# MARK-II_board.net
KiCad netlist of a schematic drawn in EAGLE
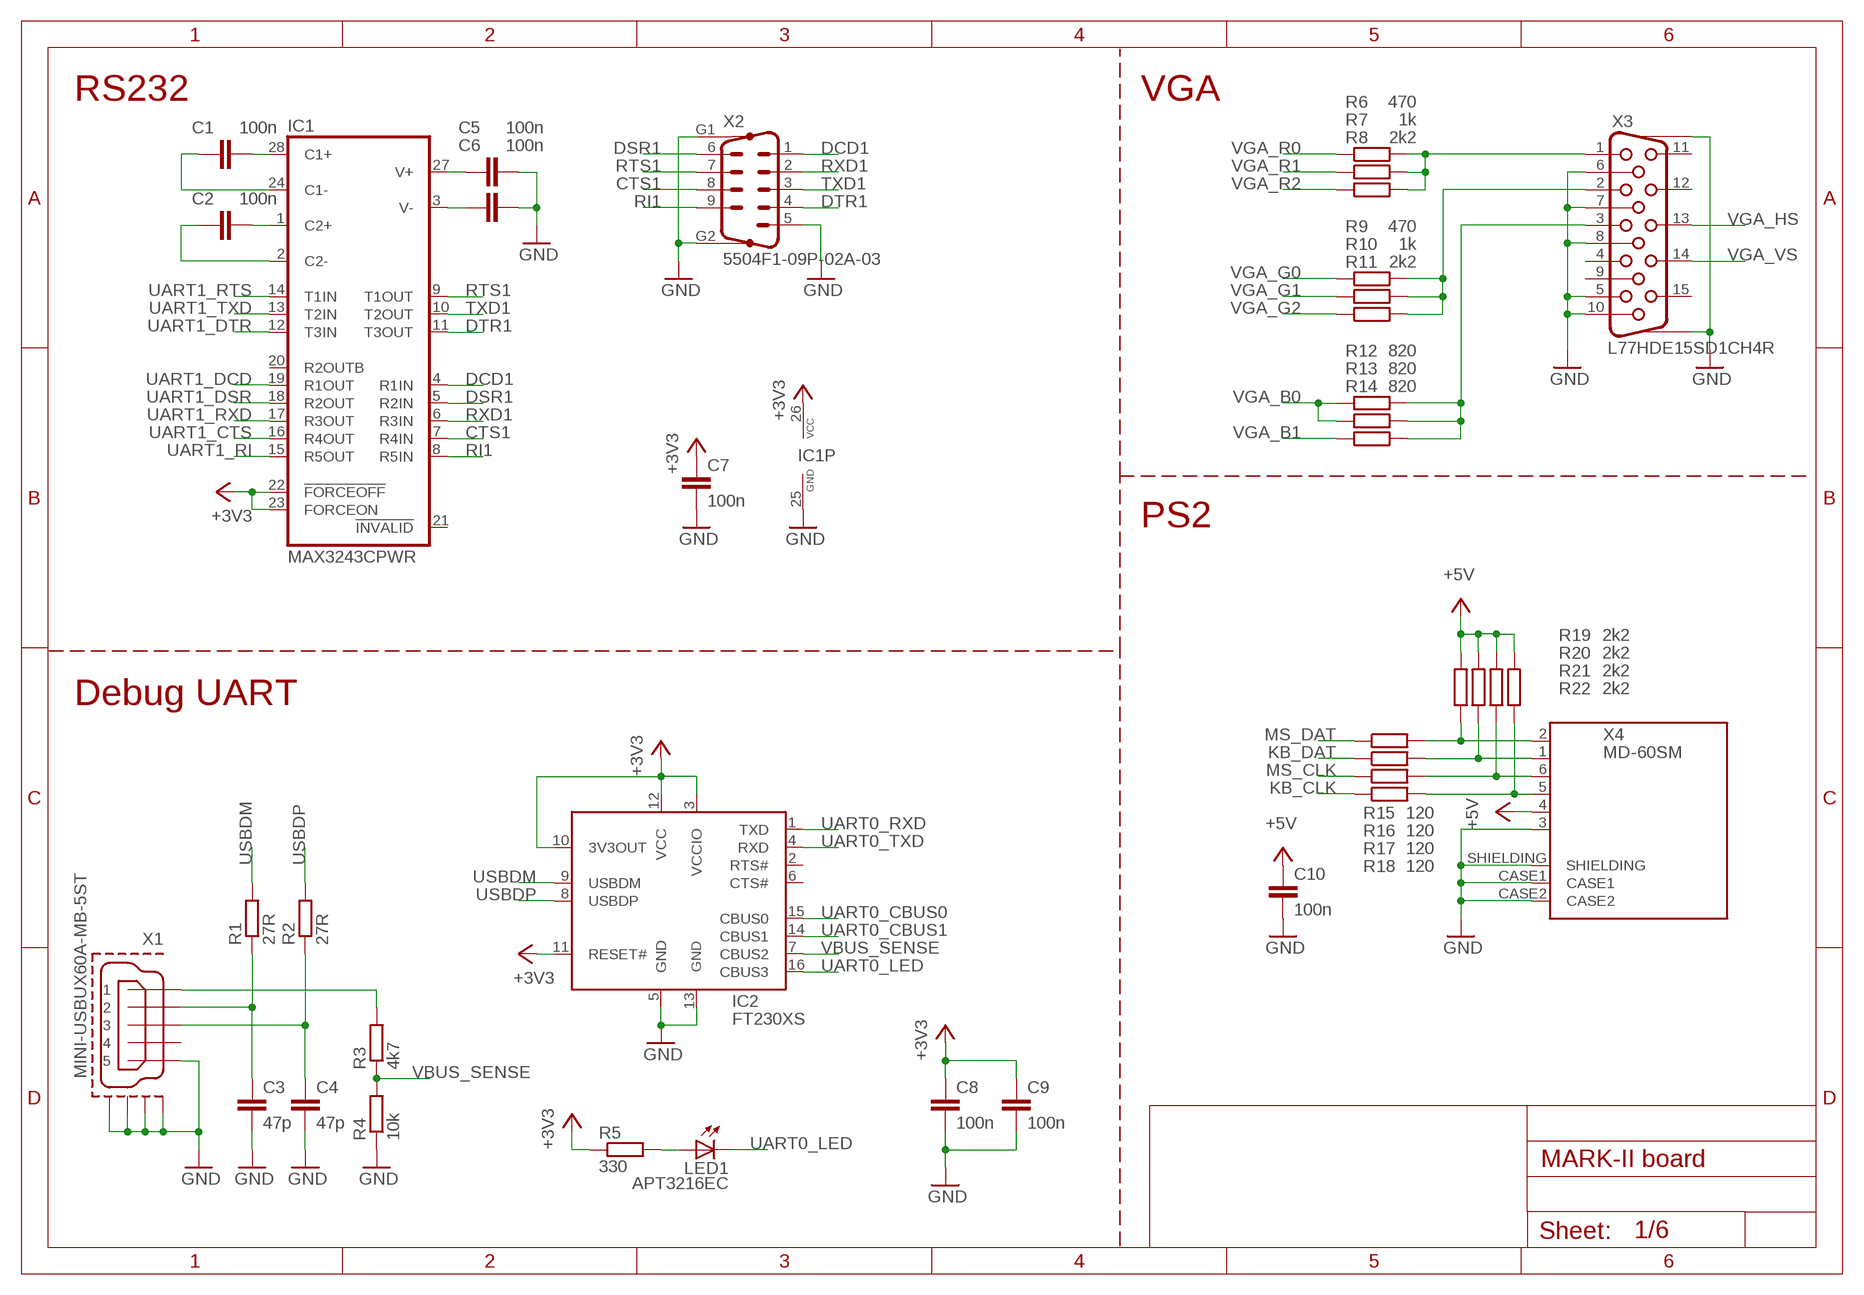
[diagram p0: schematic, sheet 1]
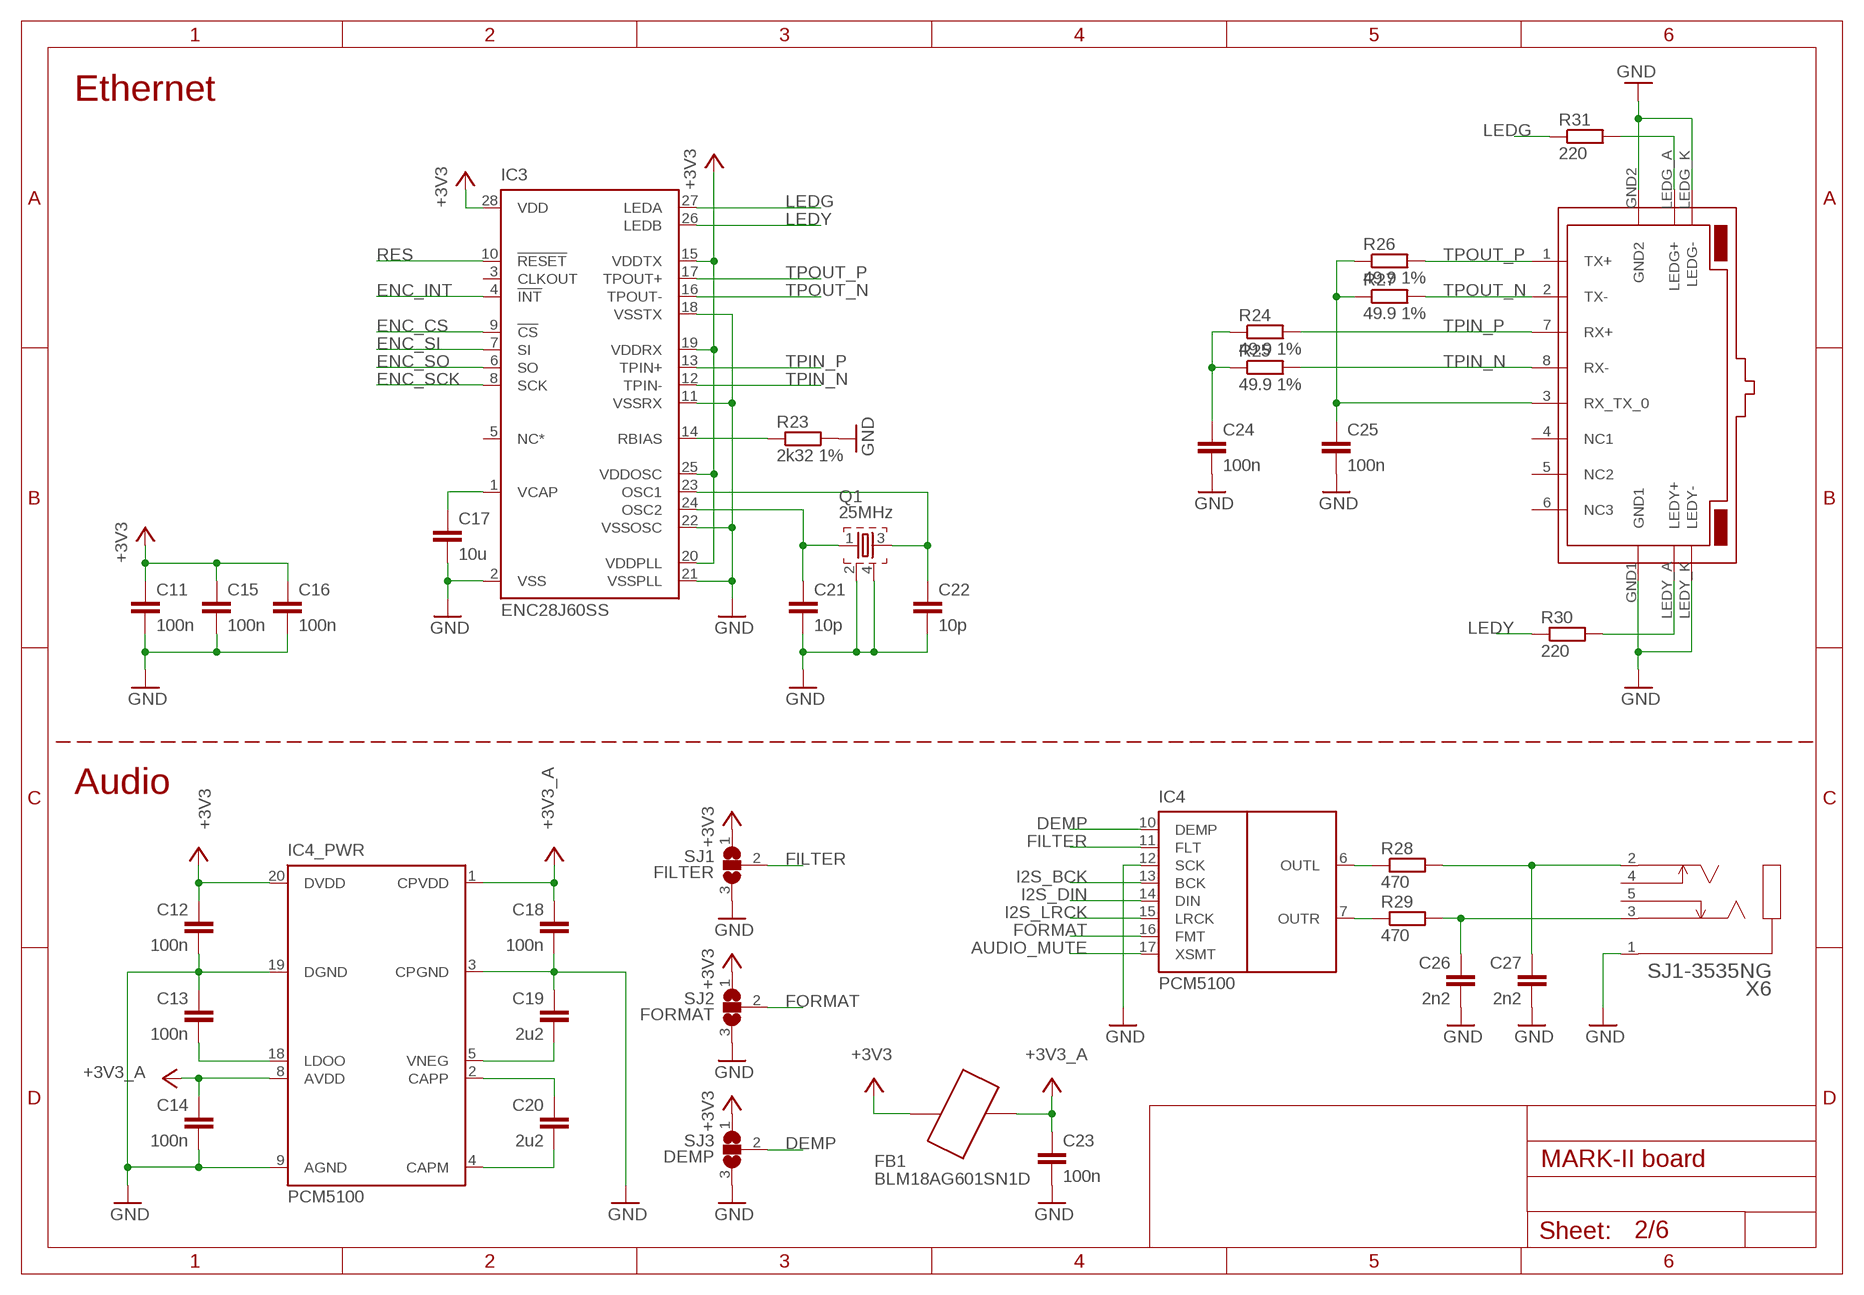
[diagram p1: schematic, sheet 2]
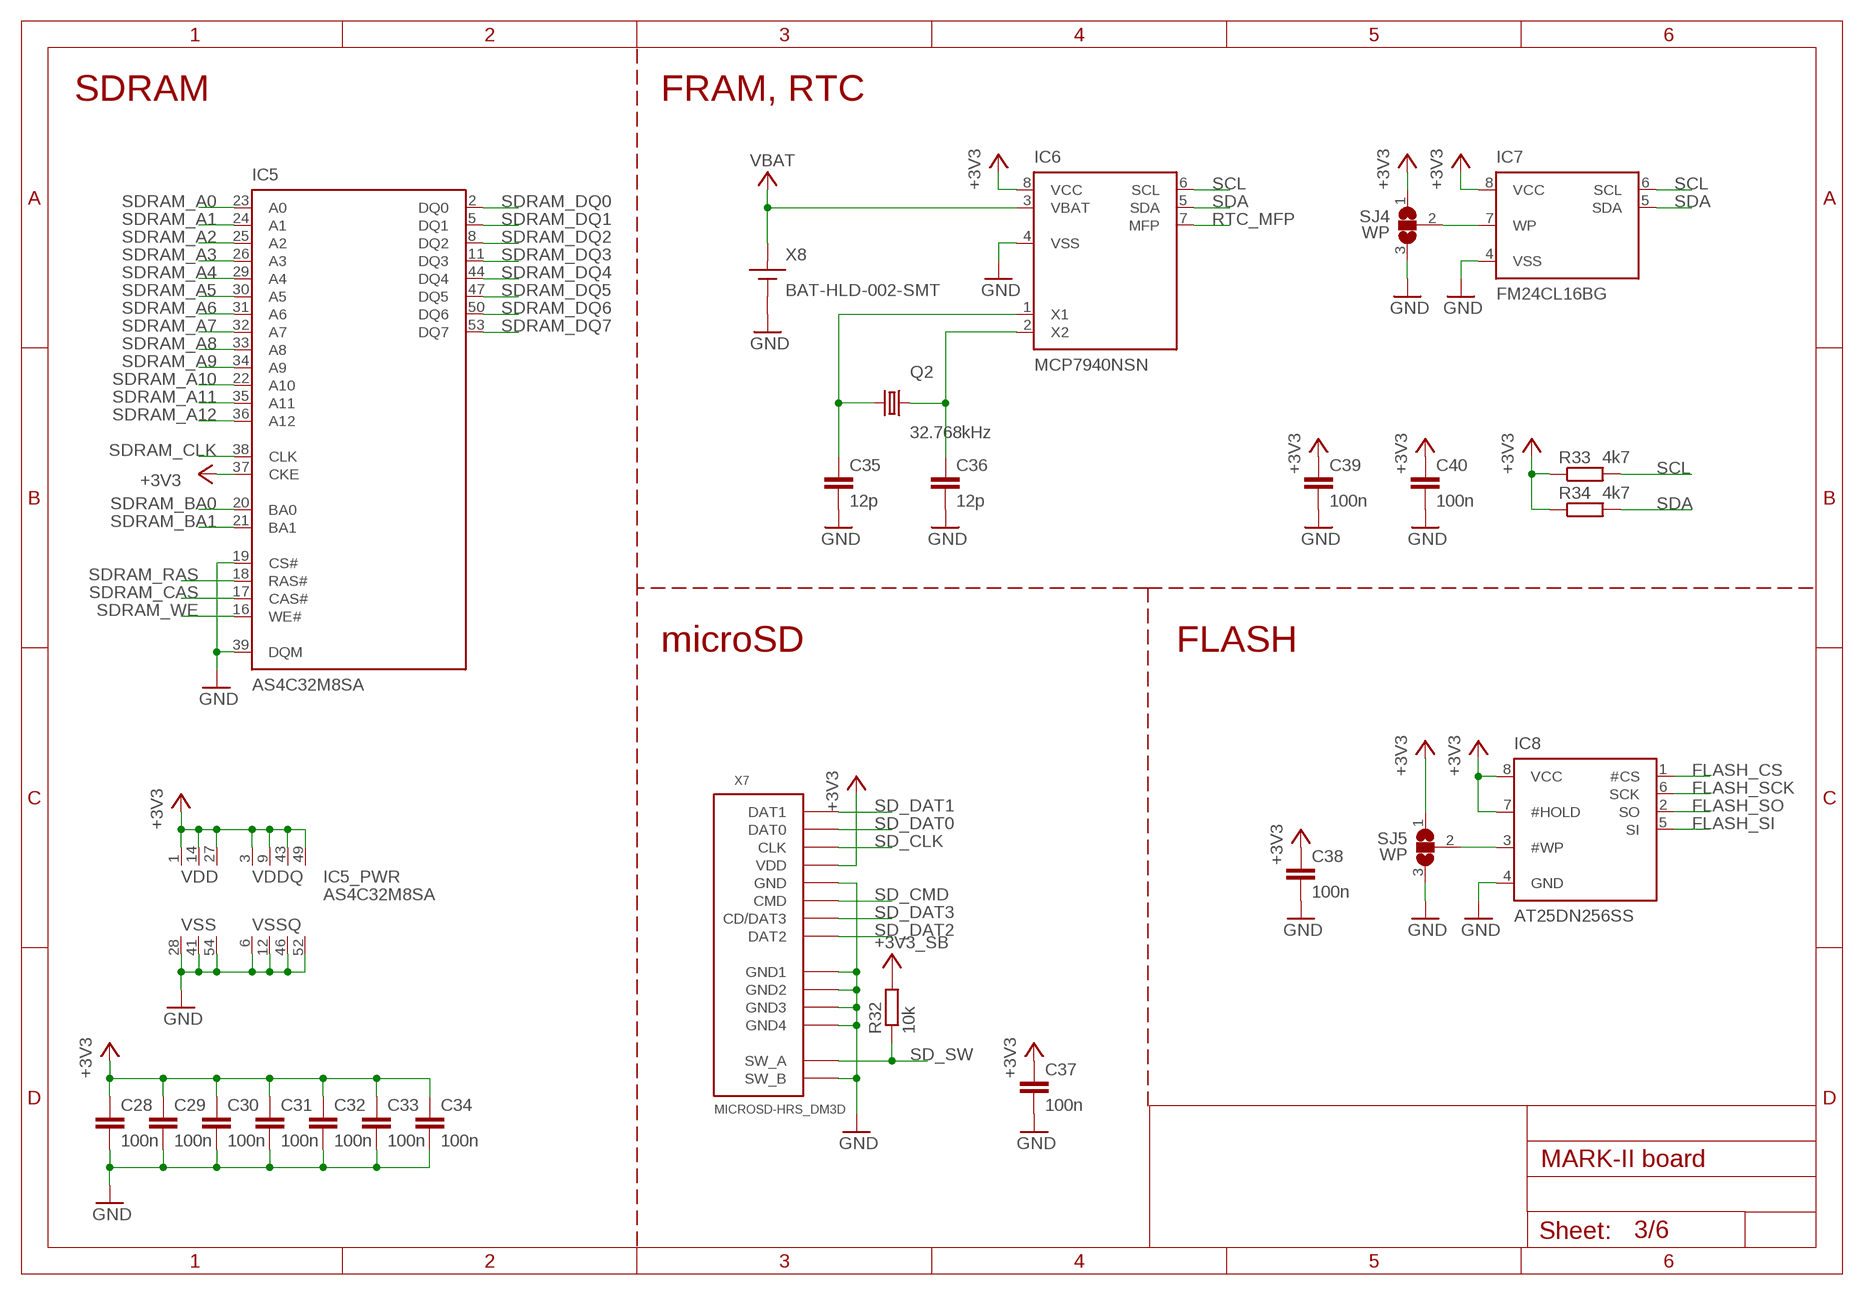
[diagram p2: schematic, sheet 3]
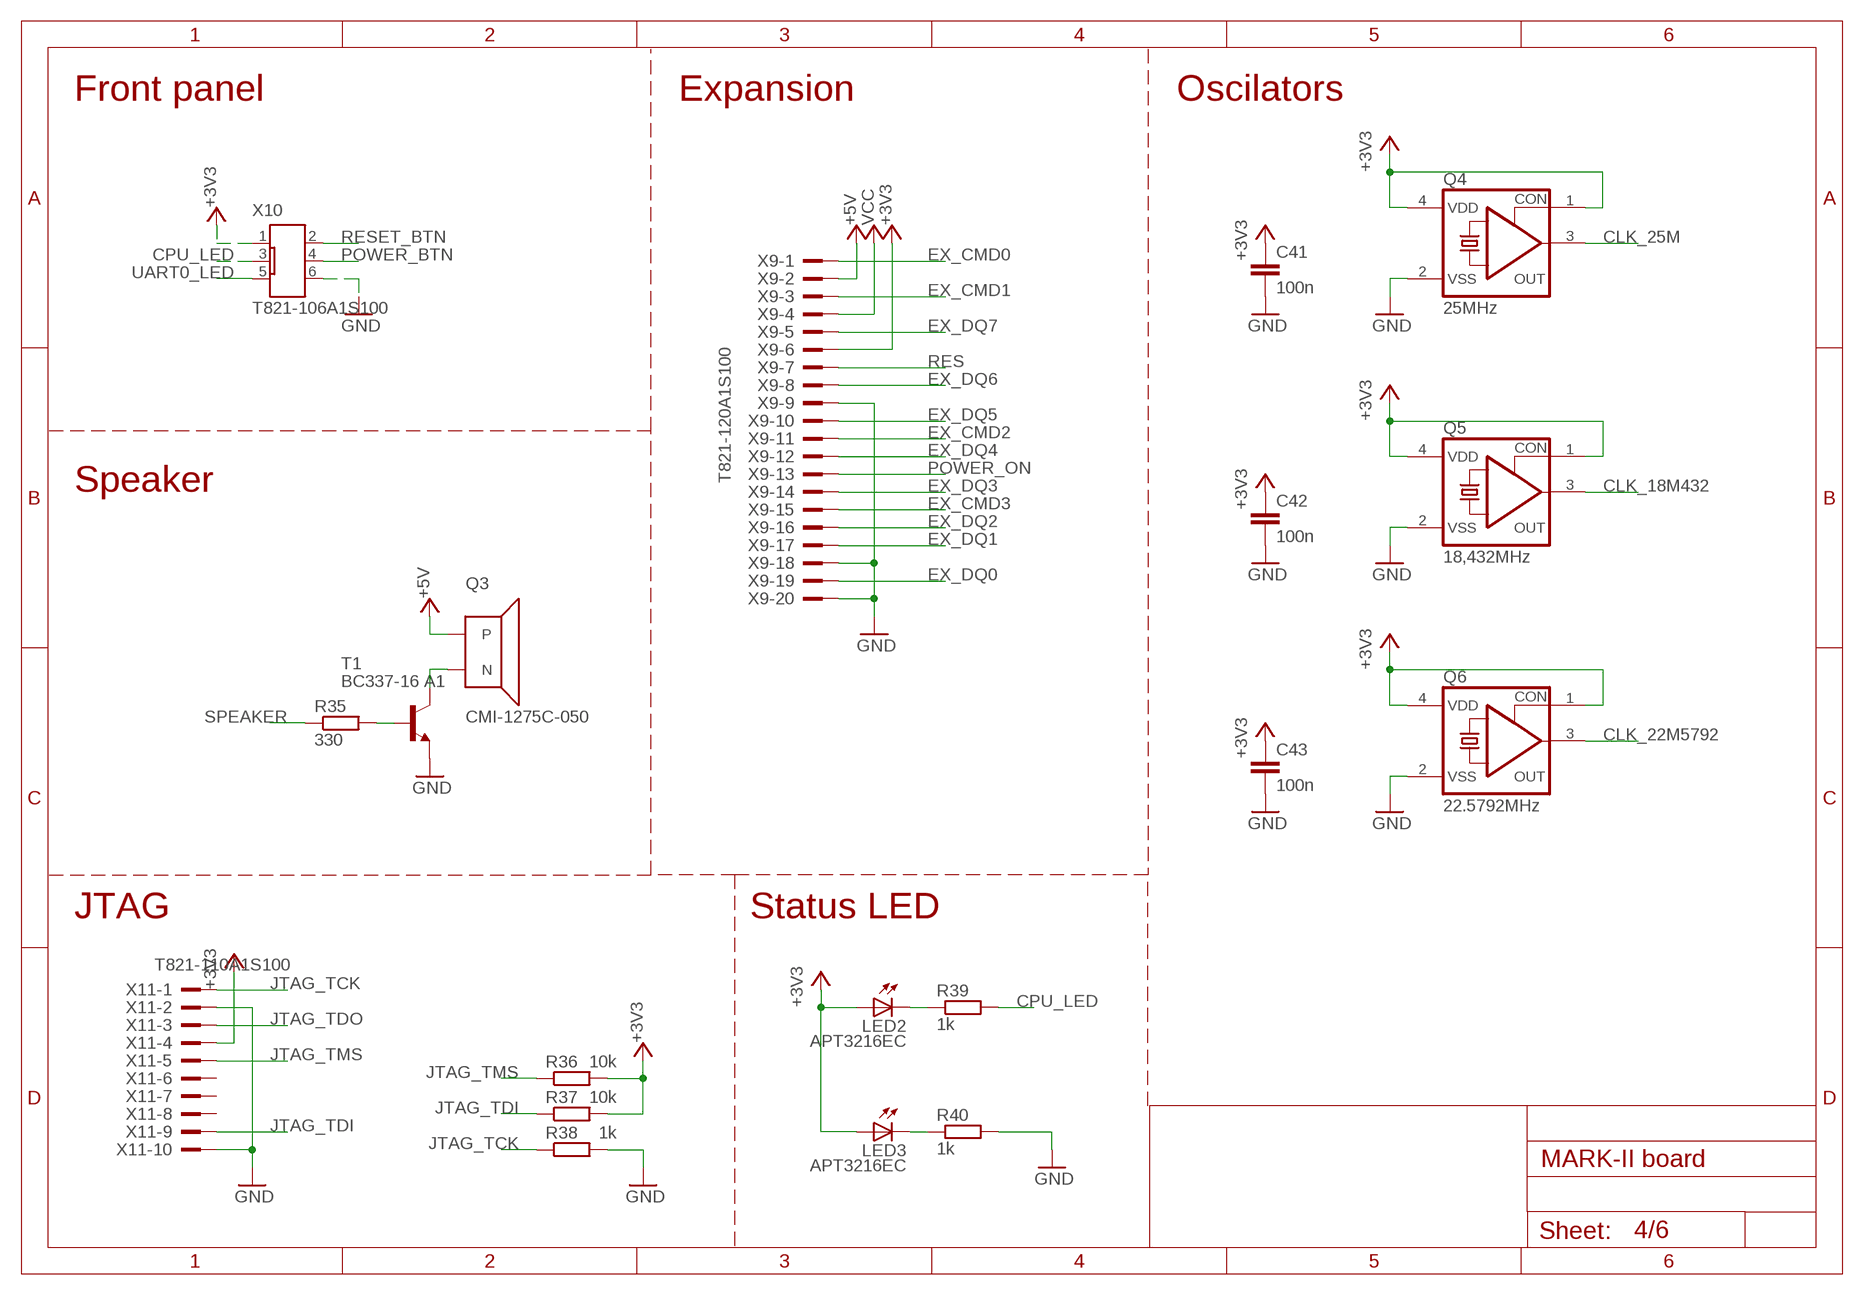
[diagram p3: schematic, sheet 4]
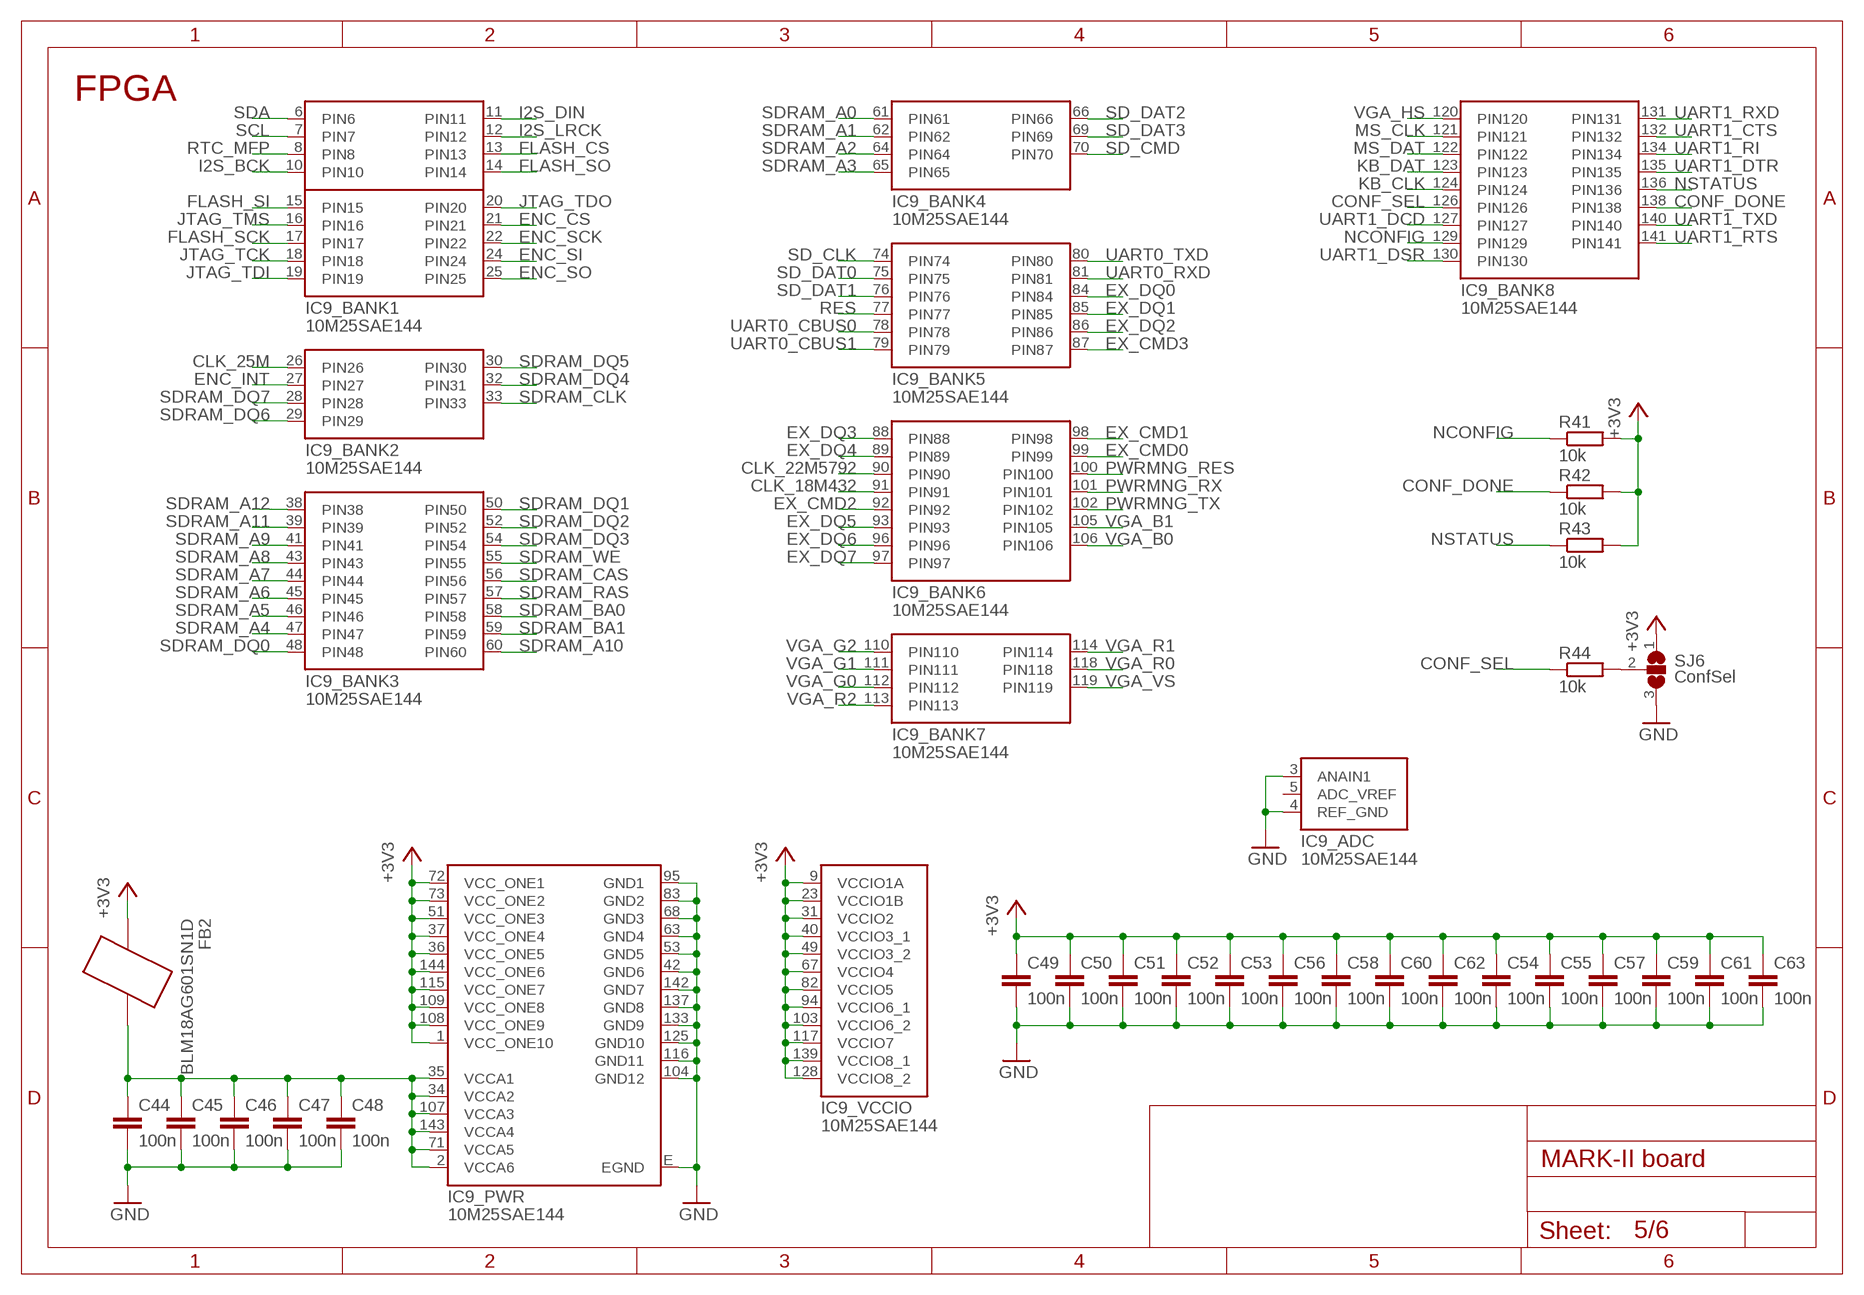
[diagram p4: schematic, sheet 5]
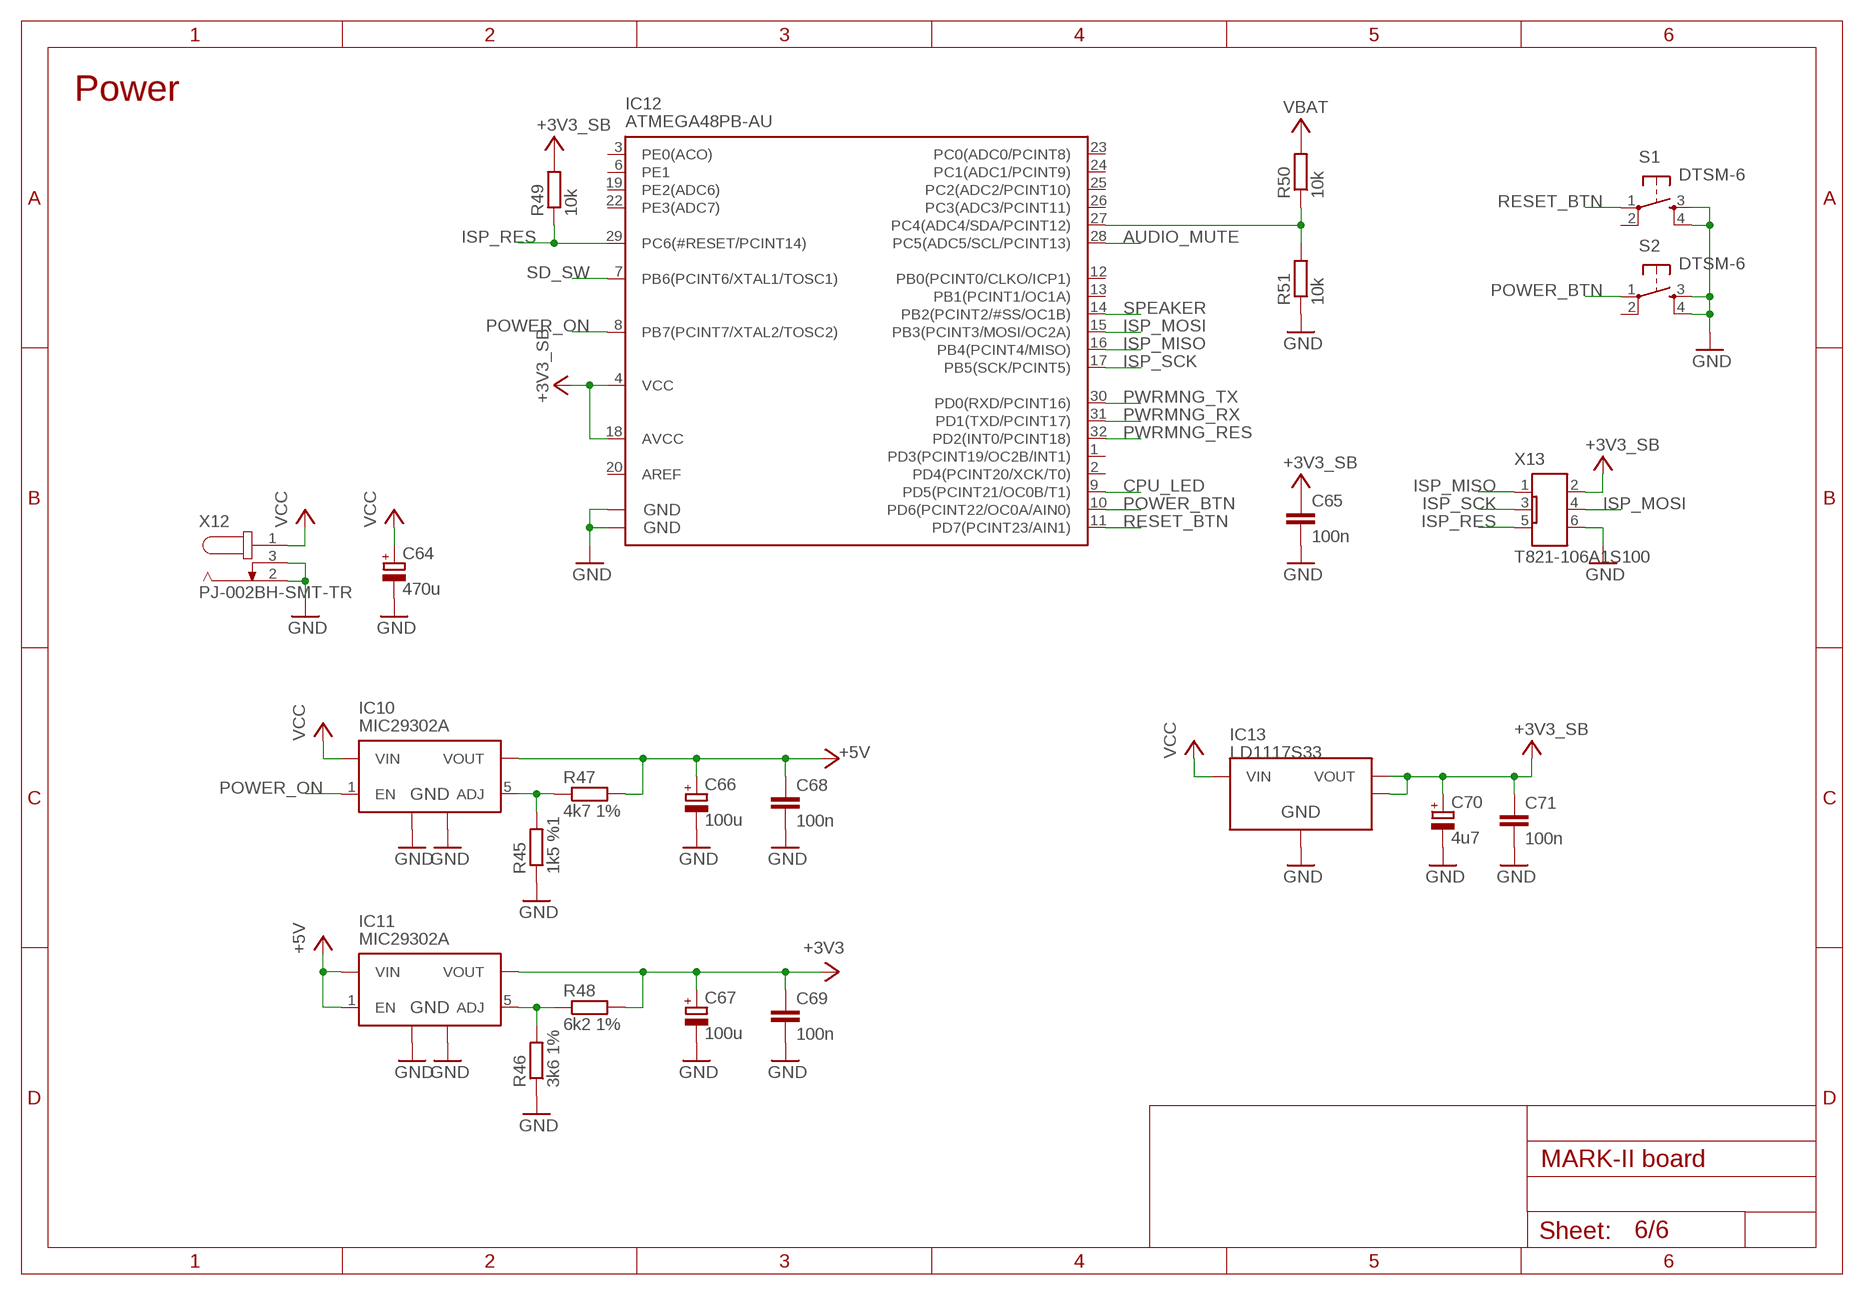
[diagram p5: schematic, sheet 6]

(export (version "E")
  (design (tool "Eeschema 10.0.6"))
  (components
    (comp (ref "C1")
      (value "100n")
      (footprint "eagle-import:C0603")
      (libsource (lib "eagle-import") (part "CC0603"))
    )
    (comp (ref "C2")
      (value "100n")
      (footprint "eagle-import:C0603")
      (libsource (lib "eagle-import") (part "CC0603"))
    )
    (comp (ref "C3")
      (value "47p")
      (footprint "eagle-import:C0603")
      (libsource (lib "eagle-import") (part "CC0603"))
    )
    (comp (ref "C4")
      (value "47p")
      (footprint "eagle-import:C0603")
      (libsource (lib "eagle-import") (part "CC0603"))
    )
    (comp (ref "C5")
      (value "100n")
      (footprint "eagle-import:C0603")
      (libsource (lib "eagle-import") (part "CC0603"))
    )
    (comp (ref "C6")
      (value "100n")
      (footprint "eagle-import:C0603")
      (libsource (lib "eagle-import") (part "CC0603"))
    )
    (comp (ref "C7")
      (value "100n")
      (footprint "eagle-import:C0603")
      (libsource (lib "eagle-import") (part "CC0603"))
    )
    (comp (ref "C8")
      (value "100n")
      (footprint "eagle-import:C0603")
      (libsource (lib "eagle-import") (part "CC0603"))
    )
    (comp (ref "C9")
      (value "100n")
      (footprint "eagle-import:C0603")
      (libsource (lib "eagle-import") (part "CC0603"))
    )
    (comp (ref "C10")
      (value "100n")
      (footprint "eagle-import:C0603")
      (libsource (lib "eagle-import") (part "CC0603"))
    )
    (comp (ref "IC1")
      (value "MAX3243CPWR")
      (footprint "eagle-import:TSSOP28")
      (fields (field (name "MOUSER") "595-MAX3243CPWR"))
      (libsource (lib "eagle-import") (part "MAX3243UI"))
    )
    (comp (ref "IC2")
      (value "FT230XS")
      (footprint "eagle-import:SSOP16")
      (libsource (lib "eagle-import") (part "FT230XS"))
    )
    (comp (ref "LED1")
      (value "APT3216EC")
      (footprint "eagle-import:1206")
      (libsource (lib "eagle-import") (part "LEDSMD"))
    )
    (comp (ref "R1")
      (value "27R")
      (footprint "eagle-import:R0603")
      (libsource (lib "eagle-import") (part "RR0603"))
    )
    (comp (ref "R2")
      (value "27R")
      (footprint "eagle-import:R0603")
      (libsource (lib "eagle-import") (part "RR0603"))
    )
    (comp (ref "R3")
      (value "4k7")
      (footprint "eagle-import:R0603")
      (libsource (lib "eagle-import") (part "RR0603"))
    )
    (comp (ref "R4")
      (value "10k")
      (footprint "eagle-import:R0603")
      (libsource (lib "eagle-import") (part "RR0603"))
    )
    (comp (ref "R5")
      (value "330")
      (footprint "eagle-import:R0603")
      (libsource (lib "eagle-import") (part "RR0603"))
    )
    (comp (ref "R6")
      (value "470")
      (footprint "eagle-import:R0603")
      (libsource (lib "eagle-import") (part "RR0603"))
    )
    (comp (ref "R7")
      (value "1k")
      (footprint "eagle-import:R0603")
      (libsource (lib "eagle-import") (part "RR0603"))
    )
    (comp (ref "R8")
      (value "2k2")
      (footprint "eagle-import:R0603")
      (libsource (lib "eagle-import") (part "RR0603"))
    )
    (comp (ref "R9")
      (value "470")
      (footprint "eagle-import:R0603")
      (libsource (lib "eagle-import") (part "RR0603"))
    )
    (comp (ref "R10")
      (value "1k")
      (footprint "eagle-import:R0603")
      (libsource (lib "eagle-import") (part "RR0603"))
    )
    (comp (ref "R11")
      (value "2k2")
      (footprint "eagle-import:R0603")
      (libsource (lib "eagle-import") (part "RR0603"))
    )
    (comp (ref "R12")
      (value "820")
      (footprint "eagle-import:R0603")
      (libsource (lib "eagle-import") (part "RR0603"))
    )
    (comp (ref "R13")
      (value "820")
      (footprint "eagle-import:R0603")
      (libsource (lib "eagle-import") (part "RR0603"))
    )
    (comp (ref "R14")
      (value "820")
      (footprint "eagle-import:R0603")
      (libsource (lib "eagle-import") (part "RR0603"))
    )
    (comp (ref "R15")
      (value "120")
      (footprint "eagle-import:R0603")
      (libsource (lib "eagle-import") (part "RR0603"))
    )
    (comp (ref "R16")
      (value "120")
      (footprint "eagle-import:R0603")
      (libsource (lib "eagle-import") (part "RR0603"))
    )
    (comp (ref "R17")
      (value "120")
      (footprint "eagle-import:R0603")
      (libsource (lib "eagle-import") (part "RR0603"))
    )
    (comp (ref "R18")
      (value "120")
      (footprint "eagle-import:R0603")
      (libsource (lib "eagle-import") (part "RR0603"))
    )
    (comp (ref "R19")
      (value "2k2")
      (footprint "eagle-import:R0603")
      (libsource (lib "eagle-import") (part "RR0603"))
    )
    (comp (ref "R20")
      (value "2k2")
      (footprint "eagle-import:R0603")
      (libsource (lib "eagle-import") (part "RR0603"))
    )
    (comp (ref "R21")
      (value "2k2")
      (footprint "eagle-import:R0603")
      (libsource (lib "eagle-import") (part "RR0603"))
    )
    (comp (ref "R22")
      (value "2k2")
      (footprint "eagle-import:R0603")
      (libsource (lib "eagle-import") (part "RR0603"))
    )
    (comp (ref "X1")
      (value "MINI-USBUX60A-MB-5ST")
      (footprint "eagle-import:UX60A-MB-5ST")
      (libsource (lib "eagle-import") (part "MINI-USBUX60A-MB-5ST"))
    )
    (comp (ref "X2")
      (value "5504F1-09P-02A-03")
      (footprint "eagle-import:M09HP")
      (libsource (lib "eagle-import") (part "M09"))
    )
    (comp (ref "X3")
      (value "L77HDE15SD1CH4R")
      (footprint "eagle-import:HDF15H")
      (libsource (lib "eagle-import") (part "HF15H"))
    )
    (comp (ref "X4")
      (value "MD-60SM")
      (footprint "eagle-import:MINIDIN_6_3GND")
      (libsource (lib "eagle-import") (part "MINIDIN_6"))
    )
    (comp (ref "C41")
      (value "100n")
      (footprint "eagle-import:C0603")
      (libsource (lib "eagle-import") (part "CC0603"))
    )
    (comp (ref "C42")
      (value "100n")
      (footprint "eagle-import:C0603")
      (libsource (lib "eagle-import") (part "CC0603"))
    )
    (comp (ref "C43")
      (value "100n")
      (footprint "eagle-import:C0603")
      (libsource (lib "eagle-import") (part "CC0603"))
    )
    (comp (ref "LED2")
      (value "APT3216EC")
      (footprint "eagle-import:1206")
      (libsource (lib "eagle-import") (part "LEDSMD"))
    )
    (comp (ref "LED3")
      (value "APT3216EC")
      (footprint "eagle-import:1206")
      (libsource (lib "eagle-import") (part "LEDSMD"))
    )
    (comp (ref "Q3")
      (value "CMI-1275C-050")
      (footprint "eagle-import:BUUZZER")
      (libsource (lib "eagle-import") (part "CMI-1275C-050"))
    )
    (comp (ref "Q4")
      (value "25MHz")
      (footprint "eagle-import:5.2X3.4-4-PAD")
      (libsource (lib "eagle-import") (part "OSC-OE-CFPS-9"))
    )
    (comp (ref "Q5")
      (value "18,432MHz")
      (footprint "eagle-import:5.2X3.4-4-PAD")
      (libsource (lib "eagle-import") (part "OSC-OE-CFPS-9"))
    )
    (comp (ref "Q6")
      (value "22.5792MHz")
      (footprint "eagle-import:5.2X3.4-4-PAD")
      (libsource (lib "eagle-import") (part "OSC-OE-CFPS-9"))
    )
    (comp (ref "R35")
      (value "330")
      (footprint "eagle-import:R0603")
      (libsource (lib "eagle-import") (part "RR0603"))
    )
    (comp (ref "R36")
      (value "10k")
      (footprint "eagle-import:R0603")
      (libsource (lib "eagle-import") (part "RR0603"))
    )
    (comp (ref "R37")
      (value "10k")
      (footprint "eagle-import:R0603")
      (libsource (lib "eagle-import") (part "RR0603"))
    )
    (comp (ref "R38")
      (value "1k")
      (footprint "eagle-import:R0603")
      (libsource (lib "eagle-import") (part "RR0603"))
    )
    (comp (ref "R39")
      (value "1k")
      (footprint "eagle-import:R0603")
      (libsource (lib "eagle-import") (part "RR0603"))
    )
    (comp (ref "R40")
      (value "1k")
      (footprint "eagle-import:R0603")
      (libsource (lib "eagle-import") (part "RR0603"))
    )
    (comp (ref "T1")
      (value "BC337-16 A1")
      (footprint "eagle-import:TO92")
      (libsource (lib "eagle-import") (part "BC337"))
    )
    (comp (ref "X9")
      (value "T821-120A1S100")
      (footprint "eagle-import:PAK100_2500-20")
      (fields (field (name "FARNELL") "2215309"))
      (libsource (lib "eagle-import") (part "2520-"))
    )
    (comp (ref "X10")
      (value "T821-106A1S100")
      (footprint "eagle-import:PAK100_2300-06")
      (libsource (lib "eagle-import") (part "IDC_2306"))
    )
    (comp (ref "X11")
      (value "T821-110A1S100")
      (footprint "eagle-import:PAK100_2500-10")
      (fields (field (name "FARNELL") "2215304"))
      (libsource (lib "eagle-import") (part "2510-"))
    )
    (comp (ref "C28")
      (value "100n")
      (footprint "eagle-import:C0603")
      (libsource (lib "eagle-import") (part "CC0603"))
    )
    (comp (ref "C29")
      (value "100n")
      (footprint "eagle-import:C0603")
      (libsource (lib "eagle-import") (part "CC0603"))
    )
    (comp (ref "C30")
      (value "100n")
      (footprint "eagle-import:C0603")
      (libsource (lib "eagle-import") (part "CC0603"))
    )
    (comp (ref "C31")
      (value "100n")
      (footprint "eagle-import:C0603")
      (libsource (lib "eagle-import") (part "CC0603"))
    )
    (comp (ref "C32")
      (value "100n")
      (footprint "eagle-import:C0603")
      (libsource (lib "eagle-import") (part "CC0603"))
    )
    (comp (ref "C33")
      (value "100n")
      (footprint "eagle-import:C0603")
      (libsource (lib "eagle-import") (part "CC0603"))
    )
    (comp (ref "C34")
      (value "100n")
      (footprint "eagle-import:C0603")
      (libsource (lib "eagle-import") (part "CC0603"))
    )
    (comp (ref "C35")
      (value "12p")
      (footprint "eagle-import:C0603")
      (libsource (lib "eagle-import") (part "CC0603"))
    )
    (comp (ref "C36")
      (value "12p")
      (footprint "eagle-import:C0603")
      (libsource (lib "eagle-import") (part "CC0603"))
    )
    (comp (ref "C37")
      (value "100n")
      (footprint "eagle-import:C0603")
      (libsource (lib "eagle-import") (part "CC0603"))
    )
    (comp (ref "C38")
      (value "100n")
      (footprint "eagle-import:C0603")
      (libsource (lib "eagle-import") (part "CC0603"))
    )
    (comp (ref "C39")
      (value "100n")
      (footprint "eagle-import:C0603")
      (libsource (lib "eagle-import") (part "CC0603"))
    )
    (comp (ref "C40")
      (value "100n")
      (footprint "eagle-import:C0603")
      (libsource (lib "eagle-import") (part "CC0603"))
    )
    (comp (ref "IC5")
      (value "AS4C32M8SA")
      (footprint "eagle-import:TSOP54")
      (fields (field (name "MOUSER") "913-AS4C32M8SA6TIN"))
      (libsource (lib "eagle-import") (part "IS42S83200"))
    )
    (comp (ref "IC6")
      (value "MCP7940NSN")
      (footprint "eagle-import:SOIC8")
      (libsource (lib "eagle-import") (part "MCP7940NSN"))
    )
    (comp (ref "IC7")
      (value "FM24CL16BG")
      (footprint "eagle-import:SOIC8")
      (libsource (lib "eagle-import") (part "FM24CL16BG"))
    )
    (comp (ref "IC8")
      (value "AT25DN256SS")
      (footprint "eagle-import:SOIC8")
      (libsource (lib "eagle-import") (part "AT25DN256SS"))
    )
    (comp (ref "Q2")
      (value "32.768kHz")
      (footprint "eagle-import:85SMX")
      (libsource (lib "eagle-import") (part "CRYSTALS-NOGND-85SMX"))
    )
    (comp (ref "R32")
      (value "10k")
      (footprint "eagle-import:R0603")
      (libsource (lib "eagle-import") (part "RR0603"))
    )
    (comp (ref "R33")
      (value "4k7")
      (footprint "eagle-import:R0603")
      (libsource (lib "eagle-import") (part "RR0603"))
    )
    (comp (ref "R34")
      (value "4k7")
      (footprint "eagle-import:R0603")
      (libsource (lib "eagle-import") (part "RR0603"))
    )
    (comp (ref "SJ4")
      (value "WP")
      (footprint "eagle-import:SJ_2")
      (libsource (lib "eagle-import") (part "SJ2W"))
    )
    (comp (ref "SJ5")
      (value "WP")
      (footprint "eagle-import:SJ_2")
      (libsource (lib "eagle-import") (part "SJ2W"))
    )
    (comp (ref "X7")
      (value "MICROSD-HRS_DM3D")
      (footprint "eagle-import:DM3D")
      (libsource (lib "eagle-import") (part "MICROSD-HRS_DM3D"))
    )
    (comp (ref "X8")
      (value "BAT-HLD-002-SMT")
      (footprint "eagle-import:BAT-HLD-002-SMT")
      (libsource (lib "eagle-import") (part "BAT-HLD-002-SMT"))
    )
    (comp (ref "C44")
      (value "100n")
      (footprint "eagle-import:C0603")
      (libsource (lib "eagle-import") (part "CC0603"))
    )
    (comp (ref "C45")
      (value "100n")
      (footprint "eagle-import:C0603")
      (libsource (lib "eagle-import") (part "CC0603"))
    )
    (comp (ref "C46")
      (value "100n")
      (footprint "eagle-import:C0603")
      (libsource (lib "eagle-import") (part "CC0603"))
    )
    (comp (ref "C47")
      (value "100n")
      (footprint "eagle-import:C0603")
      (libsource (lib "eagle-import") (part "CC0603"))
    )
    (comp (ref "C48")
      (value "100n")
      (footprint "eagle-import:C0603")
      (libsource (lib "eagle-import") (part "CC0603"))
    )
    (comp (ref "C49")
      (value "100n")
      (footprint "eagle-import:C0603")
      (libsource (lib "eagle-import") (part "CC0603"))
    )
    (comp (ref "C50")
      (value "100n")
      (footprint "eagle-import:C0603")
      (libsource (lib "eagle-import") (part "CC0603"))
    )
    (comp (ref "C51")
      (value "100n")
      (footprint "eagle-import:C0603")
      (libsource (lib "eagle-import") (part "CC0603"))
    )
    (comp (ref "C52")
      (value "100n")
      (footprint "eagle-import:C0603")
      (libsource (lib "eagle-import") (part "CC0603"))
    )
    (comp (ref "C53")
      (value "100n")
      (footprint "eagle-import:C0603")
      (libsource (lib "eagle-import") (part "CC0603"))
    )
    (comp (ref "C54")
      (value "100n")
      (footprint "eagle-import:C0603")
      (libsource (lib "eagle-import") (part "CC0603"))
    )
    (comp (ref "C55")
      (value "100n")
      (footprint "eagle-import:C0603")
      (libsource (lib "eagle-import") (part "CC0603"))
    )
    (comp (ref "C56")
      (value "100n")
      (footprint "eagle-import:C0603")
      (libsource (lib "eagle-import") (part "CC0603"))
    )
    (comp (ref "C57")
      (value "100n")
      (footprint "eagle-import:C0603")
      (libsource (lib "eagle-import") (part "CC0603"))
    )
    (comp (ref "C58")
      (value "100n")
      (footprint "eagle-import:C0603")
      (libsource (lib "eagle-import") (part "CC0603"))
    )
    (comp (ref "C59")
      (value "100n")
      (footprint "eagle-import:C0603")
      (libsource (lib "eagle-import") (part "CC0603"))
    )
    (comp (ref "C60")
      (value "100n")
      (footprint "eagle-import:C0603")
      (libsource (lib "eagle-import") (part "CC0603"))
    )
    (comp (ref "C61")
      (value "100n")
      (footprint "eagle-import:C0603")
      (libsource (lib "eagle-import") (part "CC0603"))
    )
    (comp (ref "C62")
      (value "100n")
      (footprint "eagle-import:C0603")
      (libsource (lib "eagle-import") (part "CC0603"))
    )
    (comp (ref "C63")
      (value "100n")
      (footprint "eagle-import:C0603")
      (libsource (lib "eagle-import") (part "CC0603"))
    )
    (comp (ref "FB2")
      (value "BLM18AG601SN1D")
      (footprint "eagle-import:R0603")
      (libsource (lib "eagle-import") (part "FERRITE_BEAD603"))
    )
    (comp (ref "IC9")
      (value "10M25SAE144")
      (footprint "eagle-import:EQFP144")
      (fields (field (name "MOUSER") "989-10M25SAE144C8G"))
      (libsource (lib "eagle-import") (part "10M25SAE144"))
    )
    (comp (ref "R41")
      (value "10k")
      (footprint "eagle-import:R0603")
      (libsource (lib "eagle-import") (part "RR0603"))
    )
    (comp (ref "R42")
      (value "10k")
      (footprint "eagle-import:R0603")
      (libsource (lib "eagle-import") (part "RR0603"))
    )
    (comp (ref "R43")
      (value "10k")
      (footprint "eagle-import:R0603")
      (libsource (lib "eagle-import") (part "RR0603"))
    )
    (comp (ref "R44")
      (value "10k")
      (footprint "eagle-import:R0603")
      (libsource (lib "eagle-import") (part "RR0603"))
    )
    (comp (ref "SJ6")
      (value "ConfSel")
      (footprint "eagle-import:SJ_2")
      (libsource (lib "eagle-import") (part "SJ2W"))
    )
    (comp (ref "C64")
      (value "470u")
      (footprint "eagle-import:E3,5-8")
      (libsource (lib "eagle-import") (part "C-POLE3.5-8"))
    )
    (comp (ref "C65")
      (value "100n")
      (footprint "eagle-import:C0603")
      (libsource (lib "eagle-import") (part "CC0603"))
    )
    (comp (ref "C66")
      (value "100u")
      (footprint "eagle-import:E2,5-7")
      (libsource (lib "eagle-import") (part "C-POLE2.5-7"))
    )
    (comp (ref "C67")
      (value "100u")
      (footprint "eagle-import:E2,5-7")
      (libsource (lib "eagle-import") (part "C-POLE2.5-7"))
    )
    (comp (ref "C68")
      (value "100n")
      (footprint "eagle-import:C0603")
      (libsource (lib "eagle-import") (part "CC0603"))
    )
    (comp (ref "C69")
      (value "100n")
      (footprint "eagle-import:C0603")
      (libsource (lib "eagle-import") (part "CC0603"))
    )
    (comp (ref "C70")
      (value "4u7")
      (footprint "eagle-import:E2,5-5")
      (libsource (lib "eagle-import") (part "C-POLE2.5-5"))
    )
    (comp (ref "C71")
      (value "100n")
      (footprint "eagle-import:C0603")
      (libsource (lib "eagle-import") (part "CC0603"))
    )
    (comp (ref "IC10")
      (value "MIC29302A")
      (footprint "eagle-import:D2PAK-5")
      (libsource (lib "eagle-import") (part "IFX1963TBV"))
    )
    (comp (ref "IC11")
      (value "MIC29302A")
      (footprint "eagle-import:D2PAK-5")
      (libsource (lib "eagle-import") (part "IFX1963TBV"))
    )
    (comp (ref "IC12")
      (value "ATMEGA48PB-AU")
      (footprint "eagle-import:TQFP32-08")
      (libsource (lib "eagle-import") (part "ATMEGA48PB-AU"))
    )
    (comp (ref "IC13")
      (value "LD1117S33")
      (footprint "eagle-import:SOT223")
      (libsource (lib "eagle-import") (part "LD1117S33"))
    )
    (comp (ref "R45")
      (value "1k5 %1")
      (footprint "eagle-import:R0603")
      (libsource (lib "eagle-import") (part "RR0603"))
    )
    (comp (ref "R46")
      (value "3k6 1%")
      (footprint "eagle-import:R0603")
      (libsource (lib "eagle-import") (part "RR0603"))
    )
    (comp (ref "R47")
      (value "4k7 1%")
      (footprint "eagle-import:R0603")
      (libsource (lib "eagle-import") (part "RR0603"))
    )
    (comp (ref "R48")
      (value "6k2 1%")
      (footprint "eagle-import:R0603")
      (libsource (lib "eagle-import") (part "RR0603"))
    )
    (comp (ref "R49")
      (value "10k")
      (footprint "eagle-import:R0603")
      (libsource (lib "eagle-import") (part "RR0603"))
    )
    (comp (ref "R50")
      (value "10k")
      (footprint "eagle-import:R0603")
      (libsource (lib "eagle-import") (part "RR0603"))
    )
    (comp (ref "R51")
      (value "10k")
      (footprint "eagle-import:R0603")
      (libsource (lib "eagle-import") (part "RR0603"))
    )
    (comp (ref "S1")
      (value "DTSM-6")
      (footprint "eagle-import:DTSM-6")
      (libsource (lib "eagle-import") (part "DTSM-6"))
    )
    (comp (ref "S2")
      (value "DTSM-6")
      (footprint "eagle-import:DTSM-6")
      (libsource (lib "eagle-import") (part "DTSM-6"))
    )
    (comp (ref "X12")
      (value "PJ-002BH-SMT-TR")
      (footprint "eagle-import:PJ-002BH-SMT")
      (libsource (lib "eagle-import") (part "PJ-002BH-SMT"))
    )
    (comp (ref "X13")
      (value "T821-106A1S100")
      (footprint "eagle-import:PAK100_2300-06")
      (libsource (lib "eagle-import") (part "IDC_2306"))
    )
    (comp (ref "C11")
      (value "100n")
      (footprint "eagle-import:C0603")
      (libsource (lib "eagle-import") (part "CC0603"))
    )
    (comp (ref "C12")
      (value "100n")
      (footprint "eagle-import:C0603")
      (libsource (lib "eagle-import") (part "CC0603"))
    )
    (comp (ref "C13")
      (value "100n")
      (footprint "eagle-import:C0603")
      (libsource (lib "eagle-import") (part "CC0603"))
    )
    (comp (ref "C14")
      (value "100n")
      (footprint "eagle-import:C0603")
      (libsource (lib "eagle-import") (part "CC0603"))
    )
    (comp (ref "C15")
      (value "100n")
      (footprint "eagle-import:C0603")
      (libsource (lib "eagle-import") (part "CC0603"))
    )
    (comp (ref "C16")
      (value "100n")
      (footprint "eagle-import:C0603")
      (libsource (lib "eagle-import") (part "CC0603"))
    )
    (comp (ref "C17")
      (value "10u")
      (footprint "eagle-import:C0603")
      (libsource (lib "eagle-import") (part "CC0603"))
    )
    (comp (ref "C18")
      (value "100n")
      (footprint "eagle-import:C0603")
      (libsource (lib "eagle-import") (part "CC0603"))
    )
    (comp (ref "C19")
      (value "2u2")
      (footprint "eagle-import:C0603")
      (libsource (lib "eagle-import") (part "CC0603"))
    )
    (comp (ref "C20")
      (value "2u2")
      (footprint "eagle-import:C0603")
      (libsource (lib "eagle-import") (part "CC0603"))
    )
    (comp (ref "C21")
      (value "10p")
      (footprint "eagle-import:C0603")
      (libsource (lib "eagle-import") (part "CC0603"))
    )
    (comp (ref "C22")
      (value "10p")
      (footprint "eagle-import:C0603")
      (libsource (lib "eagle-import") (part "CC0603"))
    )
    (comp (ref "C23")
      (value "100n")
      (footprint "eagle-import:C0603")
      (libsource (lib "eagle-import") (part "CC0603"))
    )
    (comp (ref "C24")
      (value "100n")
      (footprint "eagle-import:C0603")
      (libsource (lib "eagle-import") (part "CC0603"))
    )
    (comp (ref "C25")
      (value "100n")
      (footprint "eagle-import:C0603")
      (libsource (lib "eagle-import") (part "CC0603"))
    )
    (comp (ref "C26")
      (value "2n2")
      (footprint "eagle-import:C0603")
      (libsource (lib "eagle-import") (part "CC0603"))
    )
    (comp (ref "C27")
      (value "2n2")
      (footprint "eagle-import:C0603")
      (libsource (lib "eagle-import") (part "CC0603"))
    )
    (comp (ref "FB1")
      (value "BLM18AG601SN1D")
      (footprint "eagle-import:R0603")
      (libsource (lib "eagle-import") (part "FERRITE_BEAD603"))
    )
    (comp (ref "IC3")
      (value "ENC28J60SS")
      (footprint "eagle-import:SSOP28")
      (libsource (lib "eagle-import") (part "ENC28J60SS"))
    )
    (comp (ref "IC4")
      (value "PCM5100")
      (footprint "eagle-import:TSSOP20")
      (fields (field (name "MOUSER") "595-PCM5100APWR"))
      (libsource (lib "eagle-import") (part "PCM5100"))
    )
    (comp (ref "Q1")
      (value "25MHz")
      (footprint "eagle-import:3.4X2.7-4-PAD")
      (libsource (lib "eagle-import") (part "CRYSTALS-GND-LID-CFPX-180"))
    )
    (comp (ref "R23")
      (value "2k32 1%")
      (footprint "eagle-import:R0603")
      (libsource (lib "eagle-import") (part "RR0603"))
    )
    (comp (ref "R24")
      (value "49.9 1%")
      (footprint "eagle-import:R0603")
      (libsource (lib "eagle-import") (part "RR0603"))
    )
    (comp (ref "R25")
      (value "49.9 1%")
      (footprint "eagle-import:R0603")
      (libsource (lib "eagle-import") (part "RR0603"))
    )
    (comp (ref "R26")
      (value "49.9 1%")
      (footprint "eagle-import:R0603")
      (libsource (lib "eagle-import") (part "RR0603"))
    )
    (comp (ref "R27")
      (value "49.9 1%")
      (footprint "eagle-import:R0603")
      (libsource (lib "eagle-import") (part "RR0603"))
    )
    (comp (ref "R28")
      (value "470")
      (footprint "eagle-import:R0603")
      (libsource (lib "eagle-import") (part "RR0603"))
    )
    (comp (ref "R29")
      (value "470")
      (footprint "eagle-import:R0603")
      (libsource (lib "eagle-import") (part "RR0603"))
    )
    (comp (ref "R30")
      (value "220")
      (footprint "eagle-import:R0603")
      (libsource (lib "eagle-import") (part "RR0603"))
    )
    (comp (ref "R31")
      (value "220")
      (footprint "eagle-import:R0603")
      (libsource (lib "eagle-import") (part "RR0603"))
    )
    (comp (ref "SJ1")
      (value "FILTER")
      (footprint "eagle-import:SJ_2")
      (libsource (lib "eagle-import") (part "SJ2W"))
    )
    (comp (ref "SJ2")
      (value "FORMAT")
      (footprint "eagle-import:SJ_2")
      (libsource (lib "eagle-import") (part "SJ2W"))
    )
    (comp (ref "SJ3")
      (value "DEMP")
      (footprint "eagle-import:SJ_2")
      (libsource (lib "eagle-import") (part "SJ2W"))
    )
    (comp (ref "X5")
      (value "RB1-125BAG1A")
      (footprint "eagle-import:RB1-125BAG1A")
      (libsource (lib "eagle-import") (part "RB1-125BAG1A"))
    )
    (comp (ref "X6")
      (value "SJ1-3535NG")
      (footprint "eagle-import:JACK")
      (libsource (lib "eagle-import") (part "SJ1-3535NG"))
    )
  )
  (nets
    (net (code "1") (name "+3V3") (class "Default")
      (node (ref "C11") (pin "1") (pinfunction "1_1") (pintype "passive"))
      (node (ref "C12") (pin "1") (pinfunction "1_1") (pintype "passive"))
      (node (ref "C15") (pin "1") (pinfunction "1_1") (pintype "passive"))
      (node (ref "C16") (pin "1") (pinfunction "1_1") (pintype "passive"))
      (node (ref "C28") (pin "1") (pinfunction "1_1") (pintype "passive"))
      (node (ref "C29") (pin "1") (pinfunction "1_1") (pintype "passive"))
      (node (ref "C30") (pin "1") (pinfunction "1_1") (pintype "passive"))
      (node (ref "C31") (pin "1") (pinfunction "1_1") (pintype "passive"))
      (node (ref "C32") (pin "1") (pinfunction "1_1") (pintype "passive"))
      (node (ref "C33") (pin "1") (pinfunction "1_1") (pintype "passive"))
      (node (ref "C34") (pin "1") (pinfunction "1_1") (pintype "passive"))
      (node (ref "C37") (pin "1") (pinfunction "1_1") (pintype "passive"))
      (node (ref "C38") (pin "1") (pinfunction "1_1") (pintype "passive"))
      (node (ref "C39") (pin "1") (pinfunction "1_1") (pintype "passive"))
      (node (ref "C40") (pin "1") (pinfunction "1_1") (pintype "passive"))
      (node (ref "C41") (pin "1") (pinfunction "1_1") (pintype "passive"))
      (node (ref "C42") (pin "1") (pinfunction "1_1") (pintype "passive"))
      (node (ref "C43") (pin "1") (pinfunction "1_1") (pintype "passive"))
      (node (ref "C49") (pin "1") (pinfunction "1_1") (pintype "passive"))
      (node (ref "C50") (pin "1") (pinfunction "1_1") (pintype "passive"))
      (node (ref "C51") (pin "1") (pinfunction "1_1") (pintype "passive"))
      (node (ref "C52") (pin "1") (pinfunction "1_1") (pintype "passive"))
      (node (ref "C53") (pin "1") (pinfunction "1_1") (pintype "passive"))
      (node (ref "C54") (pin "1") (pinfunction "1_1") (pintype "passive"))
      (node (ref "C55") (pin "1") (pinfunction "1_1") (pintype "passive"))
      (node (ref "C56") (pin "1") (pinfunction "1_1") (pintype "passive"))
      (node (ref "C57") (pin "1") (pinfunction "1_1") (pintype "passive"))
      (node (ref "C58") (pin "1") (pinfunction "1_1") (pintype "passive"))
      (node (ref "C59") (pin "1") (pinfunction "1_1") (pintype "passive"))
      (node (ref "C60") (pin "1") (pinfunction "1_1") (pintype "passive"))
      (node (ref "C61") (pin "1") (pinfunction "1_1") (pintype "passive"))
      (node (ref "C62") (pin "1") (pinfunction "1_1") (pintype "passive"))
      (node (ref "C63") (pin "1") (pinfunction "1_1") (pintype "passive"))
      (node (ref "C67") (pin "+") (pinfunction "+_+") (pintype "passive"))
      (node (ref "C69") (pin "1") (pinfunction "1_1") (pintype "passive"))
      (node (ref "C7") (pin "1") (pinfunction "1_1") (pintype "passive"))
      (node (ref "C8") (pin "1") (pinfunction "1_1") (pintype "passive"))
      (node (ref "C9") (pin "1") (pinfunction "1_1") (pintype "passive"))
      (node (ref "FB1") (pin "1") (pinfunction "P$1_1") (pintype "passive"))
      (node (ref "FB2") (pin "1") (pinfunction "P$1_1") (pintype "passive"))
      (node (ref "IC1") (pin "22") (pinfunction "~{FORCEOFF}_22") (pintype "input"))
      (node (ref "IC1") (pin "23") (pinfunction "FORCEON_23") (pintype "input"))
      (node (ref "IC1") (pin "26") (pinfunction "VCC_26") (pintype "power_in"))
      (node (ref "IC11") (pin "4") (pinfunction "VOUT_4") (pintype "bidirectional"))
      (node (ref "IC2") (pin "10") (pinfunction "3V3OUT_10") (pintype "bidirectional"))
      (node (ref "IC2") (pin "11") (pinfunction "RESET#_11") (pintype "bidirectional"))
      (node (ref "IC2") (pin "12") (pinfunction "VCC_12") (pintype "bidirectional"))
      (node (ref "IC2") (pin "3") (pinfunction "VCCIO_3") (pintype "bidirectional"))
      (node (ref "IC3") (pin "15") (pinfunction "VDDTX_15") (pintype "input"))
      (node (ref "IC3") (pin "19") (pinfunction "VDDRX_19") (pintype "input"))
      (node (ref "IC3") (pin "20") (pinfunction "VDDPLL_20") (pintype "input"))
      (node (ref "IC3") (pin "25") (pinfunction "VDDOSC_25") (pintype "input"))
      (node (ref "IC3") (pin "28") (pinfunction "VDD_28") (pintype "input"))
      (node (ref "IC4") (pin "20") (pinfunction "DVDD_20") (pintype "bidirectional"))
      (node (ref "IC5") (pin "1") (pinfunction "VDD0_1") (pintype "power_in"))
      (node (ref "IC5") (pin "14") (pinfunction "VDD1_14") (pintype "power_in"))
      (node (ref "IC5") (pin "27") (pinfunction "VDD2_27") (pintype "power_in"))
      (node (ref "IC5") (pin "3") (pinfunction "VDDQ0_3") (pintype "power_in"))
      (node (ref "IC5") (pin "37") (pinfunction "CKE_37") (pintype "input"))
      (node (ref "IC5") (pin "43") (pinfunction "VDDQ2_43") (pintype "power_in"))
      (node (ref "IC5") (pin "49") (pinfunction "VDDQ3_49") (pintype "power_in"))
      (node (ref "IC5") (pin "9") (pinfunction "VDDQ1_9") (pintype "power_in"))
      (node (ref "IC6") (pin "8") (pinfunction "VCC_8") (pintype "bidirectional"))
      (node (ref "IC7") (pin "8") (pinfunction "VCC_8") (pintype "bidirectional"))
      (node (ref "IC8") (pin "7") (pinfunction "#HOLD_7") (pintype "bidirectional"))
      (node (ref "IC8") (pin "8") (pinfunction "VCC_8") (pintype "bidirectional"))
      (node (ref "IC9") (pin "1") (pinfunction "VCC_ONE10_1") (pintype "bidirectional"))
      (node (ref "IC9") (pin "103") (pinfunction "VCCIO6_2_103") (pintype "bidirectional"))
      (node (ref "IC9") (pin "108") (pinfunction "VCC_ONE9_108") (pintype "bidirectional"))
      (node (ref "IC9") (pin "109") (pinfunction "VCC_ONE8_109") (pintype "bidirectional"))
      (node (ref "IC9") (pin "115") (pinfunction "VCC_ONE7_115") (pintype "bidirectional"))
      (node (ref "IC9") (pin "117") (pinfunction "VCCIO7_117") (pintype "bidirectional"))
      (node (ref "IC9") (pin "128") (pinfunction "VCCIO8_2_128") (pintype "bidirectional"))
      (node (ref "IC9") (pin "139") (pinfunction "VCCIO8_1_139") (pintype "bidirectional"))
      (node (ref "IC9") (pin "144") (pinfunction "VCC_ONE6_144") (pintype "bidirectional"))
      (node (ref "IC9") (pin "23") (pinfunction "VCCIO1B_23") (pintype "bidirectional"))
      (node (ref "IC9") (pin "31") (pinfunction "VCCIO2_31") (pintype "bidirectional"))
      (node (ref "IC9") (pin "36") (pinfunction "VCC_ONE5_36") (pintype "bidirectional"))
      (node (ref "IC9") (pin "37") (pinfunction "VCC_ONE4_37") (pintype "bidirectional"))
      (node (ref "IC9") (pin "40") (pinfunction "VCCIO3_1_40") (pintype "bidirectional"))
      (node (ref "IC9") (pin "49") (pinfunction "VCCIO3_2_49") (pintype "bidirectional"))
      (node (ref "IC9") (pin "51") (pinfunction "VCC_ONE3_51") (pintype "bidirectional"))
      (node (ref "IC9") (pin "67") (pinfunction "VCCIO4_67") (pintype "bidirectional"))
      (node (ref "IC9") (pin "72") (pinfunction "VCC_ONE1_72") (pintype "bidirectional"))
      (node (ref "IC9") (pin "73") (pinfunction "VCC_ONE2_73") (pintype "bidirectional"))
      (node (ref "IC9") (pin "82") (pinfunction "VCCIO5_82") (pintype "bidirectional"))
      (node (ref "IC9") (pin "9") (pinfunction "VCCIO1A_9") (pintype "bidirectional"))
      (node (ref "IC9") (pin "94") (pinfunction "VCCIO6_1_94") (pintype "bidirectional"))
      (node (ref "LED2") (pin "A") (pinfunction "A_A") (pintype "passive"))
      (node (ref "LED3") (pin "A") (pinfunction "A_A") (pintype "passive"))
      (node (ref "Q4") (pin "1") (pinfunction "CON_1") (pintype "input"))
      (node (ref "Q4") (pin "4") (pinfunction "VDD_4") (pintype "power_in"))
      (node (ref "Q5") (pin "1") (pinfunction "CON_1") (pintype "input"))
      (node (ref "Q5") (pin "4") (pinfunction "VDD_4") (pintype "power_in"))
      (node (ref "Q6") (pin "1") (pinfunction "CON_1") (pintype "input"))
      (node (ref "Q6") (pin "4") (pinfunction "VDD_4") (pintype "power_in"))
      (node (ref "R33") (pin "1") (pinfunction "1_1") (pintype "passive"))
      (node (ref "R34") (pin "1") (pinfunction "1_1") (pintype "passive"))
      (node (ref "R36") (pin "2") (pinfunction "2_2") (pintype "passive"))
      (node (ref "R37") (pin "2") (pinfunction "2_2") (pintype "passive"))
      (node (ref "R41") (pin "2") (pinfunction "2_2") (pintype "passive"))
      (node (ref "R42") (pin "2") (pinfunction "2_2") (pintype "passive"))
      (node (ref "R43") (pin "2") (pinfunction "2_2") (pintype "passive"))
      (node (ref "R48") (pin "2") (pinfunction "2_2") (pintype "passive"))
      (node (ref "R5") (pin "1") (pinfunction "1_1") (pintype "passive"))
      (node (ref "SJ1") (pin "1") (pinfunction "1_1") (pintype "passive"))
      (node (ref "SJ2") (pin "1") (pinfunction "1_1") (pintype "passive"))
      (node (ref "SJ3") (pin "1") (pinfunction "1_1") (pintype "passive"))
      (node (ref "SJ4") (pin "1") (pinfunction "1_1") (pintype "passive"))
      (node (ref "SJ5") (pin "1") (pinfunction "1_1") (pintype "passive"))
      (node (ref "SJ6") (pin "1") (pinfunction "1_1") (pintype "passive"))
      (node (ref "X10") (pin "1") (pinfunction "1_1") (pintype "bidirectional"))
      (node (ref "X11") (pin "4") (pinfunction "KL_4") (pintype "passive"))
      (node (ref "X7") (pin "VDD") (pinfunction "VDD_VDD") (pintype "bidirectional"))
      (node (ref "X9") (pin "6") (pinfunction "KL_6") (pintype "passive"))
    )
    (net (code "2") (name "+3V3_A") (class "Default")
      (node (ref "C14") (pin "1") (pinfunction "1_1") (pintype "passive"))
      (node (ref "C18") (pin "1") (pinfunction "1_1") (pintype "passive"))
      (node (ref "C23") (pin "1") (pinfunction "1_1") (pintype "passive"))
      (node (ref "FB1") (pin "2") (pinfunction "P$2_2") (pintype "passive"))
      (node (ref "IC4") (pin "1") (pinfunction "CPVDD_1") (pintype "bidirectional"))
      (node (ref "IC4") (pin "8") (pinfunction "AVDD_8") (pintype "bidirectional"))
    )
    (net (code "3") (name "+3V3_SB") (class "Default")
      (node (ref "C65") (pin "1") (pinfunction "1_1") (pintype "passive"))
      (node (ref "C70") (pin "+") (pinfunction "+_+") (pintype "passive"))
      (node (ref "C71") (pin "1") (pinfunction "1_1") (pintype "passive"))
      (node (ref "IC12") (pin "18") (pinfunction "AVCC_18") (pintype "power_in"))
      (node (ref "IC12") (pin "4") (pinfunction "VCC_4") (pintype "power_in"))
      (node (ref "IC13") (pin "2") (pinfunction "VOUT_2") (pintype "bidirectional"))
      (node (ref "IC13") (pin "4") (pinfunction "P_4") (pintype "bidirectional"))
      (node (ref "R32") (pin "2") (pinfunction "2_2") (pintype "passive"))
      (node (ref "R49") (pin "2") (pinfunction "2_2") (pintype "passive"))
      (node (ref "X13") (pin "2") (pinfunction "2_2") (pintype "bidirectional"))
    )
    (net (code "4") (name "+5V") (class "Default")
      (node (ref "C10") (pin "1") (pinfunction "1_1") (pintype "passive"))
      (node (ref "C66") (pin "+") (pinfunction "+_+") (pintype "passive"))
      (node (ref "C68") (pin "1") (pinfunction "1_1") (pintype "passive"))
      (node (ref "IC10") (pin "4") (pinfunction "VOUT_4") (pintype "bidirectional"))
      (node (ref "IC11") (pin "1") (pinfunction "EN_1") (pintype "bidirectional"))
      (node (ref "IC11") (pin "2") (pinfunction "VIN_2") (pintype "bidirectional"))
      (node (ref "Q3") (pin "P") (pinfunction "P_P") (pintype "bidirectional"))
      (node (ref "R19") (pin "2") (pinfunction "2_2") (pintype "passive"))
      (node (ref "R20") (pin "2") (pinfunction "2_2") (pintype "passive"))
      (node (ref "R21") (pin "2") (pinfunction "2_2") (pintype "passive"))
      (node (ref "R22") (pin "2") (pinfunction "2_2") (pintype "passive"))
      (node (ref "R47") (pin "2") (pinfunction "2_2") (pintype "passive"))
      (node (ref "X4") (pin "4") (pinfunction "5_4") (pintype "bidirectional"))
      (node (ref "X9") (pin "2") (pinfunction "KL_2") (pintype "passive"))
    )
    (net (code "5") (name "AUDIO_MUTE") (class "Default")
      (node (ref "IC12") (pin "28") (pinfunction "PC5(ADC5/SCL/PCINT13)_28") (pintype "bidirectional"))
      (node (ref "IC4") (pin "17") (pinfunction "XSMT_17") (pintype "input"))
    )
    (net (code "6") (name "CLK_18M432") (class "Default")
      (node (ref "IC9") (pin "91") (pinfunction "PIN91_91") (pintype "bidirectional"))
      (node (ref "Q5") (pin "3") (pinfunction "OUT_3") (pintype "output"))
    )
    (net (code "7") (name "CLK_22M5792") (class "Default")
      (node (ref "IC9") (pin "90") (pinfunction "PIN90_90") (pintype "bidirectional"))
      (node (ref "Q6") (pin "3") (pinfunction "OUT_3") (pintype "output"))
    )
    (net (code "8") (name "CLK_25M") (class "Default")
      (node (ref "IC9") (pin "26") (pinfunction "PIN26_26") (pintype "bidirectional"))
      (node (ref "Q4") (pin "3") (pinfunction "OUT_3") (pintype "output"))
    )
    (net (code "9") (name "CONF_DONE") (class "Default")
      (node (ref "IC9") (pin "138") (pinfunction "PIN138_138") (pintype "bidirectional"))
      (node (ref "R42") (pin "1") (pinfunction "1_1") (pintype "passive"))
    )
    (net (code "10") (name "CONF_SEL") (class "Default")
      (node (ref "IC9") (pin "126") (pinfunction "PIN126_126") (pintype "bidirectional"))
      (node (ref "R44") (pin "1") (pinfunction "1_1") (pintype "passive"))
    )
    (net (code "11") (name "CPU_LED") (class "Default")
      (node (ref "IC12") (pin "9") (pinfunction "PD5(PCINT21/OC0B/T1)_9") (pintype "bidirectional"))
      (node (ref "R39") (pin "2") (pinfunction "2_2") (pintype "passive"))
      (node (ref "X10") (pin "3") (pinfunction "3_3") (pintype "bidirectional"))
    )
    (net (code "12") (name "CTS1") (class "Default")
      (node (ref "IC1") (pin "7") (pinfunction "R4IN_7") (pintype "input"))
      (node (ref "X2") (pin "8") (pinfunction "8_8") (pintype "passive"))
    )
    (net (code "13") (name "DCD1") (class "Default")
      (node (ref "IC1") (pin "4") (pinfunction "R1IN_4") (pintype "input"))
      (node (ref "X2") (pin "1") (pinfunction "1_1") (pintype "passive"))
    )
    (net (code "14") (name "DEMP") (class "Default")
      (node (ref "IC4") (pin "10") (pinfunction "DEMP_10") (pintype "input"))
      (node (ref "SJ3") (pin "2") (pinfunction "2_2") (pintype "passive"))
    )
    (net (code "15") (name "DSR1") (class "Default")
      (node (ref "IC1") (pin "5") (pinfunction "R2IN_5") (pintype "input"))
      (node (ref "X2") (pin "6") (pinfunction "6_6") (pintype "passive"))
    )
    (net (code "16") (name "DTR1") (class "Default")
      (node (ref "IC1") (pin "11") (pinfunction "T3OUT_11") (pintype "output"))
      (node (ref "X2") (pin "4") (pinfunction "4_4") (pintype "passive"))
    )
    (net (code "17") (name "ENC_CS") (class "Default")
      (node (ref "IC3") (pin "9") (pinfunction "~{CS}_9") (pintype "input"))
      (node (ref "IC9") (pin "21") (pinfunction "PIN21_21") (pintype "bidirectional"))
    )
    (net (code "18") (name "ENC_INT") (class "Default")
      (node (ref "IC3") (pin "4") (pinfunction "~{INT}_4") (pintype "output"))
      (node (ref "IC9") (pin "27") (pinfunction "PIN27_27") (pintype "bidirectional"))
    )
    (net (code "19") (name "ENC_SCK") (class "Default")
      (node (ref "IC3") (pin "8") (pinfunction "SCK_8") (pintype "input"))
      (node (ref "IC9") (pin "22") (pinfunction "PIN22_22") (pintype "bidirectional"))
    )
    (net (code "20") (name "ENC_SI") (class "Default")
      (node (ref "IC3") (pin "7") (pinfunction "SI_7") (pintype "input"))
      (node (ref "IC9") (pin "24") (pinfunction "PIN24_24") (pintype "bidirectional"))
    )
    (net (code "21") (name "ENC_SO") (class "Default")
      (node (ref "IC3") (pin "6") (pinfunction "SO_6") (pintype "output"))
      (node (ref "IC9") (pin "25") (pinfunction "PIN25_25") (pintype "bidirectional"))
    )
    (net (code "22") (name "EX_CMD0") (class "Default")
      (node (ref "IC9") (pin "99") (pinfunction "PIN99_99") (pintype "bidirectional"))
      (node (ref "X9") (pin "1") (pinfunction "KL_1") (pintype "passive"))
    )
    (net (code "23") (name "EX_CMD1") (class "Default")
      (node (ref "IC9") (pin "98") (pinfunction "PIN98_98") (pintype "bidirectional"))
      (node (ref "X9") (pin "3") (pinfunction "KL_3") (pintype "passive"))
    )
    (net (code "24") (name "EX_CMD2") (class "Default")
      (node (ref "IC9") (pin "92") (pinfunction "PIN92_92") (pintype "bidirectional"))
      (node (ref "X9") (pin "11") (pinfunction "KL_11") (pintype "passive"))
    )
    (net (code "25") (name "EX_CMD3") (class "Default")
      (node (ref "IC9") (pin "87") (pinfunction "PIN87_87") (pintype "bidirectional"))
      (node (ref "X9") (pin "15") (pinfunction "KL_15") (pintype "passive"))
    )
    (net (code "26") (name "EX_DQ0") (class "Default")
      (node (ref "IC9") (pin "84") (pinfunction "PIN84_84") (pintype "bidirectional"))
      (node (ref "X9") (pin "19") (pinfunction "KL_19") (pintype "passive"))
    )
    (net (code "27") (name "EX_DQ1") (class "Default")
      (node (ref "IC9") (pin "85") (pinfunction "PIN85_85") (pintype "bidirectional"))
      (node (ref "X9") (pin "17") (pinfunction "KL_17") (pintype "passive"))
    )
    (net (code "28") (name "EX_DQ2") (class "Default")
      (node (ref "IC9") (pin "86") (pinfunction "PIN86_86") (pintype "bidirectional"))
      (node (ref "X9") (pin "16") (pinfunction "KL_16") (pintype "passive"))
    )
    (net (code "29") (name "EX_DQ3") (class "Default")
      (node (ref "IC9") (pin "88") (pinfunction "PIN88_88") (pintype "bidirectional"))
      (node (ref "X9") (pin "14") (pinfunction "KL_14") (pintype "passive"))
    )
    (net (code "30") (name "EX_DQ4") (class "Default")
      (node (ref "IC9") (pin "89") (pinfunction "PIN89_89") (pintype "bidirectional"))
      (node (ref "X9") (pin "12") (pinfunction "KL_12") (pintype "passive"))
    )
    (net (code "31") (name "EX_DQ5") (class "Default")
      (node (ref "IC9") (pin "93") (pinfunction "PIN93_93") (pintype "bidirectional"))
      (node (ref "X9") (pin "10") (pinfunction "KL_10") (pintype "passive"))
    )
    (net (code "32") (name "EX_DQ6") (class "Default")
      (node (ref "IC9") (pin "96") (pinfunction "PIN96_96") (pintype "bidirectional"))
      (node (ref "X9") (pin "8") (pinfunction "KL_8") (pintype "passive"))
    )
    (net (code "33") (name "EX_DQ7") (class "Default")
      (node (ref "IC9") (pin "97") (pinfunction "PIN97_97") (pintype "bidirectional"))
      (node (ref "X9") (pin "5") (pinfunction "KL_5") (pintype "passive"))
    )
    (net (code "34") (name "FILTER") (class "Default")
      (node (ref "IC4") (pin "11") (pinfunction "FLT_11") (pintype "input"))
      (node (ref "SJ1") (pin "2") (pinfunction "2_2") (pintype "passive"))
    )
    (net (code "35") (name "FLASH_CS") (class "Default")
      (node (ref "IC8") (pin "1") (pinfunction "#CS_1") (pintype "bidirectional"))
      (node (ref "IC9") (pin "13") (pinfunction "PIN13_13") (pintype "bidirectional"))
    )
    (net (code "36") (name "FLASH_SCK") (class "Default")
      (node (ref "IC8") (pin "6") (pinfunction "SCK_6") (pintype "bidirectional"))
      (node (ref "IC9") (pin "17") (pinfunction "PIN17_17") (pintype "bidirectional"))
    )
    (net (code "37") (name "FLASH_SI") (class "Default")
      (node (ref "IC8") (pin "5") (pinfunction "SI_5") (pintype "bidirectional"))
      (node (ref "IC9") (pin "15") (pinfunction "PIN15_15") (pintype "bidirectional"))
    )
    (net (code "38") (name "FLASH_SO") (class "Default")
      (node (ref "IC8") (pin "2") (pinfunction "SO_2") (pintype "bidirectional"))
      (node (ref "IC9") (pin "14") (pinfunction "PIN14_14") (pintype "bidirectional"))
    )
    (net (code "39") (name "FORMAT") (class "Default")
      (node (ref "IC4") (pin "16") (pinfunction "FMT_16") (pintype "input"))
      (node (ref "SJ2") (pin "2") (pinfunction "2_2") (pintype "passive"))
    )
    (net (code "40") (name "GND") (class "Default")
      (node (ref "C10") (pin "2") (pinfunction "2_2") (pintype "passive"))
      (node (ref "C11") (pin "2") (pinfunction "2_2") (pintype "passive"))
      (node (ref "C12") (pin "2") (pinfunction "2_2") (pintype "passive"))
      (node (ref "C13") (pin "1") (pinfunction "1_1") (pintype "passive"))
      (node (ref "C14") (pin "2") (pinfunction "2_2") (pintype "passive"))
      (node (ref "C15") (pin "2") (pinfunction "2_2") (pintype "passive"))
      (node (ref "C16") (pin "2") (pinfunction "2_2") (pintype "passive"))
      (node (ref "C17") (pin "2") (pinfunction "2_2") (pintype "passive"))
      (node (ref "C18") (pin "2") (pinfunction "2_2") (pintype "passive"))
      (node (ref "C19") (pin "1") (pinfunction "1_1") (pintype "passive"))
      (node (ref "C21") (pin "2") (pinfunction "2_2") (pintype "passive"))
      (node (ref "C22") (pin "2") (pinfunction "2_2") (pintype "passive"))
      (node (ref "C23") (pin "2") (pinfunction "2_2") (pintype "passive"))
      (node (ref "C24") (pin "2") (pinfunction "2_2") (pintype "passive"))
      (node (ref "C25") (pin "2") (pinfunction "2_2") (pintype "passive"))
      (node (ref "C26") (pin "2") (pinfunction "2_2") (pintype "passive"))
      (node (ref "C27") (pin "2") (pinfunction "2_2") (pintype "passive"))
      (node (ref "C28") (pin "2") (pinfunction "2_2") (pintype "passive"))
      (node (ref "C29") (pin "2") (pinfunction "2_2") (pintype "passive"))
      (node (ref "C3") (pin "2") (pinfunction "2_2") (pintype "passive"))
      (node (ref "C30") (pin "2") (pinfunction "2_2") (pintype "passive"))
      (node (ref "C31") (pin "2") (pinfunction "2_2") (pintype "passive"))
      (node (ref "C32") (pin "2") (pinfunction "2_2") (pintype "passive"))
      (node (ref "C33") (pin "2") (pinfunction "2_2") (pintype "passive"))
      (node (ref "C34") (pin "2") (pinfunction "2_2") (pintype "passive"))
      (node (ref "C35") (pin "2") (pinfunction "2_2") (pintype "passive"))
      (node (ref "C36") (pin "2") (pinfunction "2_2") (pintype "passive"))
      (node (ref "C37") (pin "2") (pinfunction "2_2") (pintype "passive"))
      (node (ref "C38") (pin "2") (pinfunction "2_2") (pintype "passive"))
      (node (ref "C39") (pin "2") (pinfunction "2_2") (pintype "passive"))
      (node (ref "C4") (pin "2") (pinfunction "2_2") (pintype "passive"))
      (node (ref "C40") (pin "2") (pinfunction "2_2") (pintype "passive"))
      (node (ref "C41") (pin "2") (pinfunction "2_2") (pintype "passive"))
      (node (ref "C42") (pin "2") (pinfunction "2_2") (pintype "passive"))
      (node (ref "C43") (pin "2") (pinfunction "2_2") (pintype "passive"))
      (node (ref "C44") (pin "2") (pinfunction "2_2") (pintype "passive"))
      (node (ref "C45") (pin "2") (pinfunction "2_2") (pintype "passive"))
      (node (ref "C46") (pin "2") (pinfunction "2_2") (pintype "passive"))
      (node (ref "C47") (pin "2") (pinfunction "2_2") (pintype "passive"))
      (node (ref "C48") (pin "2") (pinfunction "2_2") (pintype "passive"))
      (node (ref "C49") (pin "2") (pinfunction "2_2") (pintype "passive"))
      (node (ref "C5") (pin "2") (pinfunction "2_2") (pintype "passive"))
      (node (ref "C50") (pin "2") (pinfunction "2_2") (pintype "passive"))
      (node (ref "C51") (pin "2") (pinfunction "2_2") (pintype "passive"))
      (node (ref "C52") (pin "2") (pinfunction "2_2") (pintype "passive"))
      (node (ref "C53") (pin "2") (pinfunction "2_2") (pintype "passive"))
      (node (ref "C54") (pin "2") (pinfunction "2_2") (pintype "passive"))
      (node (ref "C55") (pin "2") (pinfunction "2_2") (pintype "passive"))
      (node (ref "C56") (pin "2") (pinfunction "2_2") (pintype "passive"))
      (node (ref "C57") (pin "2") (pinfunction "2_2") (pintype "passive"))
      (node (ref "C58") (pin "2") (pinfunction "2_2") (pintype "passive"))
      (node (ref "C59") (pin "2") (pinfunction "2_2") (pintype "passive"))
      (node (ref "C6") (pin "2") (pinfunction "2_2") (pintype "passive"))
      (node (ref "C60") (pin "2") (pinfunction "2_2") (pintype "passive"))
      (node (ref "C61") (pin "2") (pinfunction "2_2") (pintype "passive"))
      (node (ref "C62") (pin "2") (pinfunction "2_2") (pintype "passive"))
      (node (ref "C63") (pin "2") (pinfunction "2_2") (pintype "passive"))
      (node (ref "C64") (pin "-") (pinfunction "-_-") (pintype "passive"))
      (node (ref "C65") (pin "2") (pinfunction "2_2") (pintype "passive"))
      (node (ref "C66") (pin "-") (pinfunction "-_-") (pintype "passive"))
      (node (ref "C67") (pin "-") (pinfunction "-_-") (pintype "passive"))
      (node (ref "C68") (pin "2") (pinfunction "2_2") (pintype "passive"))
      (node (ref "C69") (pin "2") (pinfunction "2_2") (pintype "passive"))
      (node (ref "C7") (pin "2") (pinfunction "2_2") (pintype "passive"))
      (node (ref "C70") (pin "-") (pinfunction "-_-") (pintype "passive"))
      (node (ref "C71") (pin "2") (pinfunction "2_2") (pintype "passive"))
      (node (ref "C8") (pin "2") (pinfunction "2_2") (pintype "passive"))
      (node (ref "C9") (pin "2") (pinfunction "2_2") (pintype "passive"))
      (node (ref "IC1") (pin "25") (pinfunction "GND_25") (pintype "power_in"))
      (node (ref "IC10") (pin "3") (pinfunction "GND_3") (pintype "bidirectional"))
      (node (ref "IC10") (pin "P") (pinfunction "P_P") (pintype "bidirectional"))
      (node (ref "IC11") (pin "3") (pinfunction "GND_3") (pintype "bidirectional"))
      (node (ref "IC11") (pin "P") (pinfunction "P_P") (pintype "bidirectional"))
      (node (ref "IC12") (pin "21") (pinfunction "GND_21") (pintype "power_in"))
      (node (ref "IC12") (pin "5") (pinfunction "GND_5") (pintype "power_in"))
      (node (ref "IC13") (pin "1") (pinfunction "GND_1") (pintype "bidirectional"))
      (node (ref "IC2") (pin "13") (pinfunction "GND_1_13") (pintype "bidirectional"))
      (node (ref "IC2") (pin "5") (pinfunction "GND_5") (pintype "bidirectional"))
      (node (ref "IC3") (pin "11") (pinfunction "VSSRX_11") (pintype "input"))
      (node (ref "IC3") (pin "18") (pinfunction "VSSTX_18") (pintype "input"))
      (node (ref "IC3") (pin "2") (pinfunction "VSS_2") (pintype "input"))
      (node (ref "IC3") (pin "21") (pinfunction "VSSPLL_21") (pintype "input"))
      (node (ref "IC3") (pin "22") (pinfunction "VSSOSC_22") (pintype "input"))
      (node (ref "IC4") (pin "12") (pinfunction "SCK_12") (pintype "input"))
      (node (ref "IC4") (pin "19") (pinfunction "DGND_19") (pintype "bidirectional"))
      (node (ref "IC4") (pin "3") (pinfunction "CPGND_3") (pintype "bidirectional"))
      (node (ref "IC4") (pin "9") (pinfunction "AGND_9") (pintype "bidirectional"))
      (node (ref "IC5") (pin "12") (pinfunction "VSSQ1_12") (pintype "power_in"))
      (node (ref "IC5") (pin "19") (pinfunction "CS#_19") (pintype "input"))
      (node (ref "IC5") (pin "28") (pinfunction "VSS0_28") (pintype "power_in"))
      (node (ref "IC5") (pin "39") (pinfunction "DQM_39") (pintype "input"))
      (node (ref "IC5") (pin "41") (pinfunction "VSS1_41") (pintype "power_in"))
      (node (ref "IC5") (pin "46") (pinfunction "VSSQ2_46") (pintype "power_in"))
      (node (ref "IC5") (pin "52") (pinfunction "VSSQ3_52") (pintype "power_in"))
      (node (ref "IC5") (pin "54") (pinfunction "VSS2_54") (pintype "power_in"))
      (node (ref "IC5") (pin "6") (pinfunction "VSSQ0_6") (pintype "power_in"))
      (node (ref "IC6") (pin "4") (pinfunction "VSS_4") (pintype "bidirectional"))
      (node (ref "IC7") (pin "4") (pinfunction "VSS_4") (pintype "bidirectional"))
      (node (ref "IC8") (pin "4") (pinfunction "GND_4") (pintype "bidirectional"))
      (node (ref "IC9") (pin "104") (pinfunction "GND12_104") (pintype "bidirectional"))
      (node (ref "IC9") (pin "116") (pinfunction "GND11_116") (pintype "bidirectional"))
      (node (ref "IC9") (pin "125") (pinfunction "GND10_125") (pintype "bidirectional"))
      (node (ref "IC9") (pin "133") (pinfunction "GND9_133") (pintype "bidirectional"))
      (node (ref "IC9") (pin "137") (pinfunction "GND8_137") (pintype "bidirectional"))
      (node (ref "IC9") (pin "142") (pinfunction "GND7_142") (pintype "bidirectional"))
      (node (ref "IC9") (pin "3") (pinfunction "ANAIN1_3") (pintype "bidirectional"))
      (node (ref "IC9") (pin "4") (pinfunction "REF_GND_4") (pintype "bidirectional"))
      (node (ref "IC9") (pin "42") (pinfunction "GND6_42") (pintype "bidirectional"))
      (node (ref "IC9") (pin "53") (pinfunction "GND5_53") (pintype "bidirectional"))
      (node (ref "IC9") (pin "63") (pinfunction "GND4_63") (pintype "bidirectional"))
      (node (ref "IC9") (pin "68") (pinfunction "GND3_68") (pintype "bidirectional"))
      (node (ref "IC9") (pin "83") (pinfunction "GND2_83") (pintype "bidirectional"))
      (node (ref "IC9") (pin "95") (pinfunction "GND1_95") (pintype "bidirectional"))
      (node (ref "IC9") (pin "E") (pinfunction "EGND_E") (pintype "bidirectional"))
      (node (ref "Q1") (pin "2") (pinfunction "2_2") (pintype "passive"))
      (node (ref "Q1") (pin "4") (pinfunction "4_4") (pintype "passive"))
      (node (ref "Q4") (pin "2") (pinfunction "VSS_2") (pintype "power_in"))
      (node (ref "Q5") (pin "2") (pinfunction "VSS_2") (pintype "power_in"))
      (node (ref "Q6") (pin "2") (pinfunction "VSS_2") (pintype "power_in"))
      (node (ref "R23") (pin "2") (pinfunction "2_2") (pintype "passive"))
      (node (ref "R38") (pin "2") (pinfunction "2_2") (pintype "passive"))
      (node (ref "R4") (pin "1") (pinfunction "1_1") (pintype "passive"))
      (node (ref "R40") (pin "2") (pinfunction "2_2") (pintype "passive"))
      (node (ref "R45") (pin "1") (pinfunction "1_1") (pintype "passive"))
      (node (ref "R46") (pin "1") (pinfunction "1_1") (pintype "passive"))
      (node (ref "R51") (pin "1") (pinfunction "1_1") (pintype "passive"))
      (node (ref "S1") (pin "3") (pinfunction "3_3") (pintype "passive"))
      (node (ref "S1") (pin "4") (pinfunction "4_4") (pintype "passive"))
      (node (ref "S2") (pin "3") (pinfunction "3_3") (pintype "passive"))
      (node (ref "S2") (pin "4") (pinfunction "4_4") (pintype "passive"))
      (node (ref "SJ1") (pin "3") (pinfunction "3_3") (pintype "passive"))
      (node (ref "SJ2") (pin "3") (pinfunction "3_3") (pintype "passive"))
      (node (ref "SJ3") (pin "3") (pinfunction "3_3") (pintype "passive"))
      (node (ref "SJ4") (pin "3") (pinfunction "3_3") (pintype "passive"))
      (node (ref "SJ5") (pin "3") (pinfunction "3_3") (pintype "passive"))
      (node (ref "SJ6") (pin "3") (pinfunction "3_3") (pintype "passive"))
      (node (ref "T1") (pin "1") (pinfunction "E_1") (pintype "passive"))
      (node (ref "X1") (pin "5") (pinfunction "5_5") (pintype "input"))
      (node (ref "X1") (pin "M1") (pinfunction "GND1_M1") (pintype "bidirectional"))
      (node (ref "X1") (pin "M2") (pinfunction "GND2_M2") (pintype "bidirectional"))
      (node (ref "X1") (pin "M3") (pinfunction "GND3_M3") (pintype "bidirectional"))
      (node (ref "X1") (pin "M4") (pinfunction "GND4_M4") (pintype "bidirectional"))
      (node (ref "X10") (pin "6") (pinfunction "6_6") (pintype "bidirectional"))
      (node (ref "X11") (pin "10") (pinfunction "KL_10") (pintype "passive"))
      (node (ref "X11") (pin "2") (pinfunction "KL_2") (pintype "passive"))
      (node (ref "X12") (pin "2") (pinfunction "1_2") (pintype "passive"))
      (node (ref "X12") (pin "3") (pinfunction "2_3") (pintype "passive"))
      (node (ref "X13") (pin "6") (pinfunction "6_6") (pintype "bidirectional"))
      (node (ref "X2") (pin "5") (pinfunction "5_5") (pintype "passive"))
      (node (ref "X2") (pin "G1") (pinfunction "G1_G1") (pintype "passive"))
      (node (ref "X2") (pin "G2") (pinfunction "G2_G2") (pintype "passive"))
      (node (ref "X3") (pin "10") (pinfunction "10_10") (pintype "passive"))
      (node (ref "X3") (pin "5") (pinfunction "5_5") (pintype "passive"))
      (node (ref "X3") (pin "6") (pinfunction "6_6") (pintype "passive"))
      (node (ref "X3") (pin "7") (pinfunction "7_7") (pintype "passive"))
      (node (ref "X3") (pin "8") (pinfunction "8_8") (pintype "passive"))
      (node (ref "X3") (pin "SCH1") (pinfunction "P$1_SCH1") (pintype "passive"))
      (node (ref "X3") (pin "SCH2") (pinfunction "P$2_SCH2") (pintype "passive"))
      (node (ref "X4") (pin "3") (pinfunction "6_3") (pintype "bidirectional"))
      (node (ref "X4") (pin "CASE1") (pinfunction "CASE1_CASE1") (pintype "bidirectional"))
      (node (ref "X4") (pin "CASE2") (pinfunction "CASE2_CASE2") (pintype "bidirectional"))
      (node (ref "X4") (pin "SHIELDING") (pinfunction "SHIELDING_SHIELDING") (pintype "bidirectional"))
      (node (ref "X5") (pin "GND1") (pinfunction "GND1_GND1") (pintype "power_in"))
      (node (ref "X5") (pin "GND2") (pinfunction "GND2_GND2") (pintype "power_in"))
      (node (ref "X5") (pin "LEDG_K") (pinfunction "LEDG-_LEDG_K") (pintype "bidirectional"))
      (node (ref "X5") (pin "LEDY_K") (pinfunction "LEDY-_LEDY_K") (pintype "bidirectional"))
      (node (ref "X6") (pin "1") (pinfunction "SLEEVE_1") (pintype "bidirectional"))
      (node (ref "X7") (pin "GND1") (pinfunction "GND1_GND1") (pintype "bidirectional"))
      (node (ref "X7") (pin "GND2") (pinfunction "GND2_GND2") (pintype "bidirectional"))
      (node (ref "X7") (pin "GND3") (pinfunction "GND3_GND3") (pintype "bidirectional"))
      (node (ref "X7") (pin "GND4") (pinfunction "GND4_GND4") (pintype "bidirectional"))
      (node (ref "X7") (pin "SW_B") (pinfunction "SW_B_SW_B") (pintype "bidirectional"))
      (node (ref "X7") (pin "VSS") (pinfunction "GND_VSS") (pintype "bidirectional"))
      (node (ref "X8") (pin "N") (pinfunction "N_N") (pintype "bidirectional"))
      (node (ref "X9") (pin "18") (pinfunction "KL_18") (pintype "passive"))
      (node (ref "X9") (pin "20") (pinfunction "KL_20") (pintype "passive"))
      (node (ref "X9") (pin "9") (pinfunction "KL_9") (pintype "passive"))
    )
    (net (code "41") (name "I2S_BCK") (class "Default")
      (node (ref "IC4") (pin "13") (pinfunction "BCK_13") (pintype "input"))
      (node (ref "IC9") (pin "10") (pinfunction "PIN10_10") (pintype "bidirectional"))
    )
    (net (code "42") (name "I2S_DIN") (class "Default")
      (node (ref "IC4") (pin "14") (pinfunction "DIN_14") (pintype "input"))
      (node (ref "IC9") (pin "11") (pinfunction "PIN11_11") (pintype "bidirectional"))
    )
    (net (code "43") (name "I2S_LRCK") (class "Default")
      (node (ref "IC4") (pin "15") (pinfunction "LRCK_15") (pintype "input"))
      (node (ref "IC9") (pin "12") (pinfunction "PIN12_12") (pintype "bidirectional"))
    )
    (net (code "44") (name "ISP_MISO") (class "Default")
      (node (ref "IC12") (pin "16") (pinfunction "PB4(PCINT4/MISO)_16") (pintype "bidirectional"))
      (node (ref "X13") (pin "1") (pinfunction "1_1") (pintype "bidirectional"))
    )
    (net (code "45") (name "ISP_MOSI") (class "Default")
      (node (ref "IC12") (pin "15") (pinfunction "PB3(PCINT3/MOSI/OC2A)_15") (pintype "bidirectional"))
      (node (ref "X13") (pin "4") (pinfunction "4_4") (pintype "bidirectional"))
    )
    (net (code "46") (name "ISP_RES") (class "Default")
      (node (ref "IC12") (pin "29") (pinfunction "PC6(#RESET/PCINT14)_29") (pintype "bidirectional"))
      (node (ref "R49") (pin "1") (pinfunction "1_1") (pintype "passive"))
      (node (ref "X13") (pin "5") (pinfunction "5_5") (pintype "bidirectional"))
    )
    (net (code "47") (name "ISP_SCK") (class "Default")
      (node (ref "IC12") (pin "17") (pinfunction "PB5(SCK/PCINT5)_17") (pintype "bidirectional"))
      (node (ref "X13") (pin "3") (pinfunction "3_3") (pintype "bidirectional"))
    )
    (net (code "48") (name "JTAG_TCK") (class "Default")
      (node (ref "IC9") (pin "18") (pinfunction "PIN18_18") (pintype "bidirectional"))
      (node (ref "R38") (pin "1") (pinfunction "1_1") (pintype "passive"))
      (node (ref "X11") (pin "1") (pinfunction "KL_1") (pintype "passive"))
    )
    (net (code "49") (name "JTAG_TDI") (class "Default")
      (node (ref "IC9") (pin "19") (pinfunction "PIN19_19") (pintype "bidirectional"))
      (node (ref "R37") (pin "1") (pinfunction "1_1") (pintype "passive"))
      (node (ref "X11") (pin "9") (pinfunction "KL_9") (pintype "passive"))
    )
    (net (code "50") (name "JTAG_TDO") (class "Default")
      (node (ref "IC9") (pin "20") (pinfunction "PIN20_20") (pintype "bidirectional"))
      (node (ref "X11") (pin "3") (pinfunction "KL_3") (pintype "passive"))
    )
    (net (code "51") (name "JTAG_TMS") (class "Default")
      (node (ref "IC9") (pin "16") (pinfunction "PIN16_16") (pintype "bidirectional"))
      (node (ref "R36") (pin "1") (pinfunction "1_1") (pintype "passive"))
      (node (ref "X11") (pin "5") (pinfunction "KL_5") (pintype "passive"))
    )
    (net (code "52") (name "KB_CLK") (class "Default")
      (node (ref "IC9") (pin "124") (pinfunction "PIN124_124") (pintype "bidirectional"))
      (node (ref "R18") (pin "1") (pinfunction "1_1") (pintype "passive"))
    )
    (net (code "53") (name "KB_DAT") (class "Default")
      (node (ref "IC9") (pin "123") (pinfunction "PIN123_123") (pintype "bidirectional"))
      (node (ref "R16") (pin "1") (pinfunction "1_1") (pintype "passive"))
    )
    (net (code "54") (name "LEDG") (class "Default")
      (node (ref "IC3") (pin "27") (pinfunction "LEDA_27") (pintype "output"))
      (node (ref "R31") (pin "1") (pinfunction "1_1") (pintype "passive"))
    )
    (net (code "55") (name "LEDY") (class "Default")
      (node (ref "IC3") (pin "26") (pinfunction "LEDB_26") (pintype "output"))
      (node (ref "R30") (pin "1") (pinfunction "1_1") (pintype "passive"))
    )
    (net (code "56") (name "MS_CLK") (class "Default")
      (node (ref "IC9") (pin "121") (pinfunction "PIN121_121") (pintype "bidirectional"))
      (node (ref "R17") (pin "1") (pinfunction "1_1") (pintype "passive"))
    )
    (net (code "57") (name "MS_DAT") (class "Default")
      (node (ref "IC9") (pin "122") (pinfunction "PIN122_122") (pintype "bidirectional"))
      (node (ref "R15") (pin "1") (pinfunction "1_1") (pintype "passive"))
    )
    (net (code "58") (name "NCONFIG") (class "Default")
      (node (ref "IC9") (pin "129") (pinfunction "PIN129_129") (pintype "bidirectional"))
      (node (ref "R41") (pin "1") (pinfunction "1_1") (pintype "passive"))
    )
    (net (code "59") (name "NSTATUS") (class "Default")
      (node (ref "IC9") (pin "136") (pinfunction "PIN136_136") (pintype "bidirectional"))
      (node (ref "R43") (pin "1") (pinfunction "1_1") (pintype "passive"))
    )
    (net (code "60") (name "Net-(C3-Pad1)") (class "Default")
      (node (ref "C3") (pin "1") (pinfunction "1_1") (pintype "passive"))
      (node (ref "R1") (pin "1") (pinfunction "1_1") (pintype "passive"))
      (node (ref "X1") (pin "2") (pinfunction "2_2") (pintype "input"))
    )
    (net (code "61") (name "Net-(C4-Pad1)") (class "Default")
      (node (ref "C4") (pin "1") (pinfunction "1_1") (pintype "passive"))
      (node (ref "R2") (pin "1") (pinfunction "1_1") (pintype "passive"))
      (node (ref "X1") (pin "3") (pinfunction "3_3") (pintype "input"))
    )
    (net (code "62") (name "Net-(C24-Pad1)") (class "Default")
      (node (ref "C24") (pin "1") (pinfunction "1_1") (pintype "passive"))
      (node (ref "R24") (pin "1") (pinfunction "1_1") (pintype "passive"))
      (node (ref "R25") (pin "1") (pinfunction "1_1") (pintype "passive"))
    )
    (net (code "63") (name "Net-(FB2-P$2)") (class "Default")
      (node (ref "C44") (pin "1") (pinfunction "1_1") (pintype "passive"))
      (node (ref "C45") (pin "1") (pinfunction "1_1") (pintype "passive"))
      (node (ref "C46") (pin "1") (pinfunction "1_1") (pintype "passive"))
      (node (ref "C47") (pin "1") (pinfunction "1_1") (pintype "passive"))
      (node (ref "C48") (pin "1") (pinfunction "1_1") (pintype "passive"))
      (node (ref "FB2") (pin "2") (pinfunction "P$2_2") (pintype "passive"))
      (node (ref "IC9") (pin "107") (pinfunction "VCCA3_107") (pintype "bidirectional"))
      (node (ref "IC9") (pin "143") (pinfunction "VCCA4_143") (pintype "bidirectional"))
      (node (ref "IC9") (pin "2") (pinfunction "VCCA6_2") (pintype "bidirectional"))
      (node (ref "IC9") (pin "34") (pinfunction "VCCA2_34") (pintype "bidirectional"))
      (node (ref "IC9") (pin "35") (pinfunction "VCCA1_35") (pintype "bidirectional"))
      (node (ref "IC9") (pin "71") (pinfunction "VCCA5_71") (pintype "bidirectional"))
    )
    (net (code "64") (name "Net-(IC1A-C1+)") (class "Default")
      (node (ref "C1") (pin "2") (pinfunction "2_2") (pintype "passive"))
      (node (ref "IC1") (pin "28") (pinfunction "C1+_28") (pintype "passive"))
    )
    (net (code "65") (name "Net-(IC1A-C1-)") (class "Default")
      (node (ref "C1") (pin "1") (pinfunction "1_1") (pintype "passive"))
      (node (ref "IC1") (pin "24") (pinfunction "C1-_24") (pintype "passive"))
    )
    (net (code "66") (name "Net-(IC1A-C2+)") (class "Default")
      (node (ref "C2") (pin "2") (pinfunction "2_2") (pintype "passive"))
      (node (ref "IC1") (pin "1") (pinfunction "C2+_1") (pintype "passive"))
    )
    (net (code "67") (name "Net-(IC1A-C2-)") (class "Default")
      (node (ref "C2") (pin "1") (pinfunction "1_1") (pintype "passive"))
      (node (ref "IC1") (pin "2") (pinfunction "C2-_2") (pintype "passive"))
    )
    (net (code "68") (name "Net-(IC1A-V+)") (class "Default")
      (node (ref "C5") (pin "1") (pinfunction "1_1") (pintype "passive"))
      (node (ref "IC1") (pin "27") (pinfunction "V+_27") (pintype "passive"))
    )
    (net (code "69") (name "Net-(IC1A-V-)") (class "Default")
      (node (ref "C6") (pin "1") (pinfunction "1_1") (pintype "passive"))
      (node (ref "IC1") (pin "3") (pinfunction "V-_3") (pintype "passive"))
    )
    (net (code "70") (name "Net-(IC3-OSC1)") (class "Default")
      (node (ref "C22") (pin "1") (pinfunction "1_1") (pintype "passive"))
      (node (ref "IC3") (pin "23") (pinfunction "OSC1_23") (pintype "input"))
      (node (ref "Q1") (pin "3") (pinfunction "3_3") (pintype "passive"))
    )
    (net (code "71") (name "Net-(IC3-OSC2)") (class "Default")
      (node (ref "C21") (pin "1") (pinfunction "1_1") (pintype "passive"))
      (node (ref "IC3") (pin "24") (pinfunction "OSC2_24") (pintype "output"))
      (node (ref "Q1") (pin "1") (pinfunction "1_1") (pintype "passive"))
    )
    (net (code "72") (name "Net-(IC3-RBIAS)") (class "Default")
      (node (ref "IC3") (pin "14") (pinfunction "RBIAS_14") (pintype "input"))
      (node (ref "R23") (pin "1") (pinfunction "1_1") (pintype "passive"))
    )
    (net (code "73") (name "Net-(IC3-VCAP)") (class "Default")
      (node (ref "C17") (pin "1") (pinfunction "1_1") (pintype "passive"))
      (node (ref "IC3") (pin "1") (pinfunction "VCAP_1") (pintype "input"))
    )
    (net (code "74") (name "Net-(IC4A-OUTL)") (class "Default")
      (node (ref "IC4") (pin "6") (pinfunction "OUTL_6") (pintype "bidirectional"))
      (node (ref "R28") (pin "1") (pinfunction "1_1") (pintype "passive"))
    )
    (net (code "75") (name "Net-(IC4A-OUTR)") (class "Default")
      (node (ref "IC4") (pin "7") (pinfunction "OUTR_7") (pintype "bidirectional"))
      (node (ref "R29") (pin "1") (pinfunction "1_1") (pintype "passive"))
    )
    (net (code "76") (name "Net-(IC4B-CAPM)") (class "Default")
      (node (ref "C20") (pin "2") (pinfunction "2_2") (pintype "passive"))
      (node (ref "IC4") (pin "4") (pinfunction "CAPM_4") (pintype "bidirectional"))
    )
    (net (code "77") (name "Net-(IC4B-CAPP)") (class "Default")
      (node (ref "C20") (pin "1") (pinfunction "1_1") (pintype "passive"))
      (node (ref "IC4") (pin "2") (pinfunction "CAPP_2") (pintype "bidirectional"))
    )
    (net (code "78") (name "Net-(IC4B-LDOO)") (class "Default")
      (node (ref "C13") (pin "2") (pinfunction "2_2") (pintype "passive"))
      (node (ref "IC4") (pin "18") (pinfunction "LDOO_18") (pintype "bidirectional"))
    )
    (net (code "79") (name "Net-(IC4B-VNEG)") (class "Default")
      (node (ref "C19") (pin "2") (pinfunction "2_2") (pintype "passive"))
      (node (ref "IC4") (pin "5") (pinfunction "VNEG_5") (pintype "bidirectional"))
    )
    (net (code "80") (name "Net-(IC6-X1)") (class "Default")
      (node (ref "C35") (pin "1") (pinfunction "1_1") (pintype "passive"))
      (node (ref "IC6") (pin "1") (pinfunction "X1_1") (pintype "bidirectional"))
      (node (ref "Q2") (pin "4") (pinfunction "2_4") (pintype "passive"))
    )
    (net (code "81") (name "Net-(IC6-X2)") (class "Default")
      (node (ref "C36") (pin "1") (pinfunction "1_1") (pintype "passive"))
      (node (ref "IC6") (pin "2") (pinfunction "X2_2") (pintype "bidirectional"))
      (node (ref "Q2") (pin "1") (pinfunction "1_1") (pintype "passive"))
    )
    (net (code "82") (name "Net-(IC7-WP)") (class "Default")
      (node (ref "IC7") (pin "7") (pinfunction "WP_7") (pintype "bidirectional"))
      (node (ref "SJ4") (pin "2") (pinfunction "2_2") (pintype "passive"))
    )
    (net (code "83") (name "Net-(IC8-#WP)") (class "Default")
      (node (ref "IC8") (pin "3") (pinfunction "#WP_3") (pintype "bidirectional"))
      (node (ref "SJ5") (pin "2") (pinfunction "2_2") (pintype "passive"))
    )
    (net (code "84") (name "Net-(IC10-ADJ)") (class "Default")
      (node (ref "IC10") (pin "5") (pinfunction "ADJ_5") (pintype "bidirectional"))
      (node (ref "R45") (pin "2") (pinfunction "2_2") (pintype "passive"))
      (node (ref "R47") (pin "1") (pinfunction "1_1") (pintype "passive"))
    )
    (net (code "85") (name "Net-(IC11-ADJ)") (class "Default")
      (node (ref "IC11") (pin "5") (pinfunction "ADJ_5") (pintype "bidirectional"))
      (node (ref "R46") (pin "2") (pinfunction "2_2") (pintype "passive"))
      (node (ref "R48") (pin "1") (pinfunction "1_1") (pintype "passive"))
    )
    (net (code "86") (name "Net-(IC12-PC4(ADC4{slash}SDA{slash}PCINT12))") (class "Default")
      (node (ref "IC12") (pin "27") (pinfunction "PC4(ADC4/SDA/PCINT12)_27") (pintype "bidirectional"))
      (node (ref "R50") (pin "1") (pinfunction "1_1") (pintype "passive"))
      (node (ref "R51") (pin "2") (pinfunction "2_2") (pintype "passive"))
    )
    (net (code "87") (name "Net-(LED1-PadA)") (class "Default")
      (node (ref "LED1") (pin "A") (pinfunction "A_A") (pintype "passive"))
      (node (ref "R5") (pin "2") (pinfunction "2_2") (pintype "passive"))
    )
    (net (code "88") (name "Net-(LED2-PadC)") (class "Default")
      (node (ref "LED2") (pin "C") (pinfunction "C_C") (pintype "passive"))
      (node (ref "R39") (pin "1") (pinfunction "1_1") (pintype "passive"))
    )
    (net (code "89") (name "Net-(LED3-PadC)") (class "Default")
      (node (ref "LED3") (pin "C") (pinfunction "C_C") (pintype "passive"))
      (node (ref "R40") (pin "1") (pinfunction "1_1") (pintype "passive"))
    )
    (net (code "90") (name "Net-(R3-Pad2)") (class "Default")
      (node (ref "R3") (pin "2") (pinfunction "2_2") (pintype "passive"))
      (node (ref "X1") (pin "1") (pinfunction "1_1") (pintype "input"))
    )
    (net (code "91") (name "Net-(R6-Pad2)") (class "Default")
      (node (ref "R6") (pin "2") (pinfunction "2_2") (pintype "passive"))
      (node (ref "R7") (pin "2") (pinfunction "2_2") (pintype "passive"))
      (node (ref "R8") (pin "2") (pinfunction "2_2") (pintype "passive"))
      (node (ref "X3") (pin "1") (pinfunction "1_1") (pintype "passive"))
    )
    (net (code "92") (name "Net-(R10-Pad2)") (class "Default")
      (node (ref "R10") (pin "2") (pinfunction "2_2") (pintype "passive"))
      (node (ref "R11") (pin "2") (pinfunction "2_2") (pintype "passive"))
      (node (ref "R9") (pin "2") (pinfunction "2_2") (pintype "passive"))
      (node (ref "X3") (pin "2") (pinfunction "2_2") (pintype "passive"))
    )
    (net (code "93") (name "Net-(R12-Pad2)") (class "Default")
      (node (ref "R12") (pin "2") (pinfunction "2_2") (pintype "passive"))
      (node (ref "R13") (pin "2") (pinfunction "2_2") (pintype "passive"))
      (node (ref "R14") (pin "2") (pinfunction "2_2") (pintype "passive"))
      (node (ref "X3") (pin "3") (pinfunction "3_3") (pintype "passive"))
    )
    (net (code "94") (name "Net-(R44-Pad2)") (class "Default")
      (node (ref "R44") (pin "2") (pinfunction "2_2") (pintype "passive"))
      (node (ref "SJ6") (pin "2") (pinfunction "2_2") (pintype "passive"))
    )
    (net (code "95") (name "Net-(T1-B)") (class "Default")
      (node (ref "R35") (pin "2") (pinfunction "2_2") (pintype "passive"))
      (node (ref "T1") (pin "2") (pinfunction "B_2") (pintype "passive"))
    )
    (net (code "96") (name "Net-(T1-C)") (class "Default")
      (node (ref "Q3") (pin "N") (pinfunction "N_N") (pintype "bidirectional"))
      (node (ref "T1") (pin "3") (pinfunction "C_3") (pintype "passive"))
    )
    (net (code "97") (name "Net-(X4-1)") (class "Default")
      (node (ref "R15") (pin "2") (pinfunction "2_2") (pintype "passive"))
      (node (ref "R19") (pin "1") (pinfunction "1_1") (pintype "passive"))
      (node (ref "X4") (pin "2") (pinfunction "1_2") (pintype "bidirectional"))
    )
    (net (code "98") (name "Net-(X4-2)") (class "Default")
      (node (ref "R16") (pin "2") (pinfunction "2_2") (pintype "passive"))
      (node (ref "R20") (pin "1") (pinfunction "1_1") (pintype "passive"))
      (node (ref "X4") (pin "1") (pinfunction "2_1") (pintype "bidirectional"))
    )
    (net (code "99") (name "Net-(X4-3)") (class "Default")
      (node (ref "R17") (pin "2") (pinfunction "2_2") (pintype "passive"))
      (node (ref "R21") (pin "1") (pinfunction "1_1") (pintype "passive"))
      (node (ref "X4") (pin "6") (pinfunction "3_6") (pintype "bidirectional"))
    )
    (net (code "100") (name "Net-(X4-4)") (class "Default")
      (node (ref "R18") (pin "2") (pinfunction "2_2") (pintype "passive"))
      (node (ref "R22") (pin "1") (pinfunction "1_1") (pintype "passive"))
      (node (ref "X4") (pin "5") (pinfunction "4_5") (pintype "bidirectional"))
    )
    (net (code "101") (name "Net-(X5-LEDG+)") (class "Default")
      (node (ref "R31") (pin "2") (pinfunction "2_2") (pintype "passive"))
      (node (ref "X5") (pin "LEDG_A") (pinfunction "LEDG+_LEDG_A") (pintype "bidirectional"))
    )
    (net (code "102") (name "Net-(X5-LEDY+)") (class "Default")
      (node (ref "R30") (pin "2") (pinfunction "2_2") (pintype "passive"))
      (node (ref "X5") (pin "LEDY_A") (pinfunction "LEDY+_LEDY_A") (pintype "bidirectional"))
    )
    (net (code "103") (name "Net-(X5-RX_TX_0)") (class "Default")
      (node (ref "C25") (pin "1") (pinfunction "1_1") (pintype "passive"))
      (node (ref "R26") (pin "1") (pinfunction "1_1") (pintype "passive"))
      (node (ref "R27") (pin "1") (pinfunction "1_1") (pintype "passive"))
      (node (ref "X5") (pin "3") (pinfunction "RX_TX_0_3") (pintype "bidirectional"))
    )
    (net (code "104") (name "Net-(X6-RING)") (class "Default")
      (node (ref "C26") (pin "1") (pinfunction "1_1") (pintype "passive"))
      (node (ref "R29") (pin "2") (pinfunction "2_2") (pintype "passive"))
      (node (ref "X6") (pin "3") (pinfunction "RING_3") (pintype "bidirectional"))
    )
    (net (code "105") (name "Net-(X6-TIP)") (class "Default")
      (node (ref "C27") (pin "1") (pinfunction "1_1") (pintype "passive"))
      (node (ref "R28") (pin "2") (pinfunction "2_2") (pintype "passive"))
      (node (ref "X6") (pin "2") (pinfunction "TIP_2") (pintype "bidirectional"))
    )
    (net (code "106") (name "POWER_BTN") (class "Default")
      (node (ref "IC12") (pin "10") (pinfunction "PD6(PCINT22/OC0A/AIN0)_10") (pintype "bidirectional"))
      (node (ref "S2") (pin "1") (pinfunction "1_1") (pintype "passive"))
      (node (ref "X10") (pin "4") (pinfunction "4_4") (pintype "bidirectional"))
    )
    (net (code "107") (name "POWER_ON") (class "Default")
      (node (ref "IC10") (pin "1") (pinfunction "EN_1") (pintype "bidirectional"))
      (node (ref "IC12") (pin "8") (pinfunction "PB7(PCINT7/XTAL2/TOSC2)_8") (pintype "bidirectional"))
      (node (ref "X9") (pin "13") (pinfunction "KL_13") (pintype "passive"))
    )
    (net (code "108") (name "PWRMNG_RES") (class "Default")
      (node (ref "IC12") (pin "32") (pinfunction "PD2(INT0/PCINT18)_32") (pintype "bidirectional"))
      (node (ref "IC9") (pin "100") (pinfunction "PIN100_100") (pintype "bidirectional"))
    )
    (net (code "109") (name "PWRMNG_RX") (class "Default")
      (node (ref "IC12") (pin "31") (pinfunction "PD1(TXD/PCINT17)_31") (pintype "bidirectional"))
      (node (ref "IC9") (pin "101") (pinfunction "PIN101_101") (pintype "bidirectional"))
    )
    (net (code "110") (name "PWRMNG_TX") (class "Default")
      (node (ref "IC12") (pin "30") (pinfunction "PD0(RXD/PCINT16)_30") (pintype "bidirectional"))
      (node (ref "IC9") (pin "102") (pinfunction "PIN102_102") (pintype "bidirectional"))
    )
    (net (code "111") (name "RES") (class "Default")
      (node (ref "IC3") (pin "10") (pinfunction "~{RESET}_10") (pintype "input"))
      (node (ref "IC9") (pin "77") (pinfunction "PIN77_77") (pintype "bidirectional"))
      (node (ref "X9") (pin "7") (pinfunction "KL_7") (pintype "passive"))
    )
    (net (code "112") (name "RESET_BTN") (class "Default")
      (node (ref "IC12") (pin "11") (pinfunction "PD7(PCINT23/AIN1)_11") (pintype "bidirectional"))
      (node (ref "S1") (pin "1") (pinfunction "1_1") (pintype "passive"))
      (node (ref "X10") (pin "2") (pinfunction "2_2") (pintype "bidirectional"))
    )
    (net (code "113") (name "RI1") (class "Default")
      (node (ref "IC1") (pin "8") (pinfunction "R5IN_8") (pintype "input"))
      (node (ref "X2") (pin "9") (pinfunction "9_9") (pintype "passive"))
    )
    (net (code "114") (name "RTC_MFP") (class "Default")
      (node (ref "IC6") (pin "7") (pinfunction "MFP_7") (pintype "bidirectional"))
      (node (ref "IC9") (pin "8") (pinfunction "PIN8_8") (pintype "bidirectional"))
    )
    (net (code "115") (name "RTS1") (class "Default")
      (node (ref "IC1") (pin "9") (pinfunction "T1OUT_9") (pintype "output"))
      (node (ref "X2") (pin "7") (pinfunction "7_7") (pintype "passive"))
    )
    (net (code "116") (name "RXD1") (class "Default")
      (node (ref "IC1") (pin "6") (pinfunction "R3IN_6") (pintype "input"))
      (node (ref "X2") (pin "2") (pinfunction "2_2") (pintype "passive"))
    )
    (net (code "117") (name "SCL") (class "Default")
      (node (ref "IC6") (pin "6") (pinfunction "SCL_6") (pintype "bidirectional"))
      (node (ref "IC7") (pin "6") (pinfunction "SCL_6") (pintype "bidirectional"))
      (node (ref "IC9") (pin "7") (pinfunction "PIN7_7") (pintype "bidirectional"))
      (node (ref "R33") (pin "2") (pinfunction "2_2") (pintype "passive"))
    )
    (net (code "118") (name "SDA") (class "Default")
      (node (ref "IC6") (pin "5") (pinfunction "SDA_5") (pintype "bidirectional"))
      (node (ref "IC7") (pin "5") (pinfunction "SDA_5") (pintype "bidirectional"))
      (node (ref "IC9") (pin "6") (pinfunction "PIN6_6") (pintype "bidirectional"))
      (node (ref "R34") (pin "2") (pinfunction "2_2") (pintype "passive"))
    )
    (net (code "119") (name "SDRAM_A0") (class "Default")
      (node (ref "IC5") (pin "23") (pinfunction "A0_23") (pintype "input"))
      (node (ref "IC9") (pin "61") (pinfunction "PIN61_61") (pintype "bidirectional"))
    )
    (net (code "120") (name "SDRAM_A1") (class "Default")
      (node (ref "IC5") (pin "24") (pinfunction "A1_24") (pintype "input"))
      (node (ref "IC9") (pin "62") (pinfunction "PIN62_62") (pintype "bidirectional"))
    )
    (net (code "121") (name "SDRAM_A2") (class "Default")
      (node (ref "IC5") (pin "25") (pinfunction "A2_25") (pintype "input"))
      (node (ref "IC9") (pin "64") (pinfunction "PIN64_64") (pintype "bidirectional"))
    )
    (net (code "122") (name "SDRAM_A3") (class "Default")
      (node (ref "IC5") (pin "26") (pinfunction "A3_26") (pintype "input"))
      (node (ref "IC9") (pin "65") (pinfunction "PIN65_65") (pintype "bidirectional"))
    )
    (net (code "123") (name "SDRAM_A4") (class "Default")
      (node (ref "IC5") (pin "29") (pinfunction "A4_29") (pintype "input"))
      (node (ref "IC9") (pin "47") (pinfunction "PIN47_47") (pintype "bidirectional"))
    )
    (net (code "124") (name "SDRAM_A5") (class "Default")
      (node (ref "IC5") (pin "30") (pinfunction "A5_30") (pintype "input"))
      (node (ref "IC9") (pin "46") (pinfunction "PIN46_46") (pintype "bidirectional"))
    )
    (net (code "125") (name "SDRAM_A6") (class "Default")
      (node (ref "IC5") (pin "31") (pinfunction "A6_31") (pintype "input"))
      (node (ref "IC9") (pin "45") (pinfunction "PIN45_45") (pintype "bidirectional"))
    )
    (net (code "126") (name "SDRAM_A7") (class "Default")
      (node (ref "IC5") (pin "32") (pinfunction "A7_32") (pintype "input"))
      (node (ref "IC9") (pin "44") (pinfunction "PIN44_44") (pintype "bidirectional"))
    )
    (net (code "127") (name "SDRAM_A8") (class "Default")
      (node (ref "IC5") (pin "33") (pinfunction "A8_33") (pintype "input"))
      (node (ref "IC9") (pin "43") (pinfunction "PIN43_43") (pintype "bidirectional"))
    )
    (net (code "128") (name "SDRAM_A9") (class "Default")
      (node (ref "IC5") (pin "34") (pinfunction "A9_34") (pintype "input"))
      (node (ref "IC9") (pin "41") (pinfunction "PIN41_41") (pintype "bidirectional"))
    )
    (net (code "129") (name "SDRAM_A10") (class "Default")
      (node (ref "IC5") (pin "22") (pinfunction "A10_22") (pintype "input"))
      (node (ref "IC9") (pin "60") (pinfunction "PIN60_60") (pintype "bidirectional"))
    )
    (net (code "130") (name "SDRAM_A11") (class "Default")
      (node (ref "IC5") (pin "35") (pinfunction "A11_35") (pintype "input"))
      (node (ref "IC9") (pin "39") (pinfunction "PIN39_39") (pintype "bidirectional"))
    )
    (net (code "131") (name "SDRAM_A12") (class "Default")
      (node (ref "IC5") (pin "36") (pinfunction "A12_36") (pintype "input"))
      (node (ref "IC9") (pin "38") (pinfunction "PIN38_38") (pintype "bidirectional"))
    )
    (net (code "132") (name "SDRAM_BA0") (class "Default")
      (node (ref "IC5") (pin "20") (pinfunction "BA0_20") (pintype "input"))
      (node (ref "IC9") (pin "58") (pinfunction "PIN58_58") (pintype "bidirectional"))
    )
    (net (code "133") (name "SDRAM_BA1") (class "Default")
      (node (ref "IC5") (pin "21") (pinfunction "BA1_21") (pintype "input"))
      (node (ref "IC9") (pin "59") (pinfunction "PIN59_59") (pintype "bidirectional"))
    )
    (net (code "134") (name "SDRAM_CAS") (class "Default")
      (node (ref "IC5") (pin "17") (pinfunction "CAS#_17") (pintype "input"))
      (node (ref "IC9") (pin "56") (pinfunction "PIN56_56") (pintype "bidirectional"))
    )
    (net (code "135") (name "SDRAM_CLK") (class "Default")
      (node (ref "IC5") (pin "38") (pinfunction "CLK_38") (pintype "input"))
      (node (ref "IC9") (pin "33") (pinfunction "PIN33_33") (pintype "bidirectional"))
    )
    (net (code "136") (name "SDRAM_DQ0") (class "Default")
      (node (ref "IC5") (pin "2") (pinfunction "DQ0_2") (pintype "bidirectional"))
      (node (ref "IC9") (pin "48") (pinfunction "PIN48_48") (pintype "bidirectional"))
    )
    (net (code "137") (name "SDRAM_DQ1") (class "Default")
      (node (ref "IC5") (pin "5") (pinfunction "DQ1_5") (pintype "bidirectional"))
      (node (ref "IC9") (pin "50") (pinfunction "PIN50_50") (pintype "bidirectional"))
    )
    (net (code "138") (name "SDRAM_DQ2") (class "Default")
      (node (ref "IC5") (pin "8") (pinfunction "DQ2_8") (pintype "bidirectional"))
      (node (ref "IC9") (pin "52") (pinfunction "PIN52_52") (pintype "bidirectional"))
    )
    (net (code "139") (name "SDRAM_DQ3") (class "Default")
      (node (ref "IC5") (pin "11") (pinfunction "DQ3_11") (pintype "bidirectional"))
      (node (ref "IC9") (pin "54") (pinfunction "PIN54_54") (pintype "bidirectional"))
    )
    (net (code "140") (name "SDRAM_DQ4") (class "Default")
      (node (ref "IC5") (pin "44") (pinfunction "DQ4_44") (pintype "bidirectional"))
      (node (ref "IC9") (pin "32") (pinfunction "PIN31_32") (pintype "bidirectional"))
    )
    (net (code "141") (name "SDRAM_DQ5") (class "Default")
      (node (ref "IC5") (pin "47") (pinfunction "DQ5_47") (pintype "bidirectional"))
      (node (ref "IC9") (pin "30") (pinfunction "PIN30_30") (pintype "bidirectional"))
    )
    (net (code "142") (name "SDRAM_DQ6") (class "Default")
      (node (ref "IC5") (pin "50") (pinfunction "DQ6_50") (pintype "bidirectional"))
      (node (ref "IC9") (pin "29") (pinfunction "PIN29_29") (pintype "bidirectional"))
    )
    (net (code "143") (name "SDRAM_DQ7") (class "Default")
      (node (ref "IC5") (pin "53") (pinfunction "DQ7_53") (pintype "bidirectional"))
      (node (ref "IC9") (pin "28") (pinfunction "PIN28_28") (pintype "bidirectional"))
    )
    (net (code "144") (name "SDRAM_RAS") (class "Default")
      (node (ref "IC5") (pin "18") (pinfunction "RAS#_18") (pintype "input"))
      (node (ref "IC9") (pin "57") (pinfunction "PIN57_57") (pintype "bidirectional"))
    )
    (net (code "145") (name "SDRAM_WE") (class "Default")
      (node (ref "IC5") (pin "16") (pinfunction "WE#_16") (pintype "input"))
      (node (ref "IC9") (pin "55") (pinfunction "PIN55_55") (pintype "bidirectional"))
    )
    (net (code "146") (name "SD_CLK") (class "Default")
      (node (ref "IC9") (pin "74") (pinfunction "PIN74_74") (pintype "bidirectional"))
      (node (ref "X7") (pin "CLK") (pinfunction "CLK_CLK") (pintype "bidirectional"))
    )
    (net (code "147") (name "SD_CMD") (class "Default")
      (node (ref "IC9") (pin "70") (pinfunction "PIN70_70") (pintype "bidirectional"))
      (node (ref "X7") (pin "CMD") (pinfunction "CMD_CMD") (pintype "bidirectional"))
    )
    (net (code "148") (name "SD_DAT0") (class "Default")
      (node (ref "IC9") (pin "75") (pinfunction "PIN75_75") (pintype "bidirectional"))
      (node (ref "X7") (pin "DAT0") (pinfunction "DAT0_DAT0") (pintype "bidirectional"))
    )
    (net (code "149") (name "SD_DAT1") (class "Default")
      (node (ref "IC9") (pin "76") (pinfunction "PIN76_76") (pintype "bidirectional"))
      (node (ref "X7") (pin "DAT1") (pinfunction "DAT1_DAT1") (pintype "bidirectional"))
    )
    (net (code "150") (name "SD_DAT2") (class "Default")
      (node (ref "IC9") (pin "66") (pinfunction "PIN66_66") (pintype "bidirectional"))
      (node (ref "X7") (pin "DAT2") (pinfunction "DAT2_DAT2") (pintype "bidirectional"))
    )
    (net (code "151") (name "SD_DAT3") (class "Default")
      (node (ref "IC9") (pin "69") (pinfunction "PIN69_69") (pintype "bidirectional"))
      (node (ref "X7") (pin "CD/DAT3") (pinfunction "CD/DAT3_CD/DAT3") (pintype "bidirectional"))
    )
    (net (code "152") (name "SD_SW") (class "Default")
      (node (ref "IC12") (pin "7") (pinfunction "PB6(PCINT6/XTAL1/TOSC1)_7") (pintype "bidirectional"))
      (node (ref "R32") (pin "1") (pinfunction "1_1") (pintype "passive"))
      (node (ref "X7") (pin "SW_A") (pinfunction "SW_A_SW_A") (pintype "bidirectional"))
    )
    (net (code "153") (name "SPEAKER") (class "Default")
      (node (ref "IC12") (pin "14") (pinfunction "PB2(PCINT2/#SS/OC1B)_14") (pintype "bidirectional"))
      (node (ref "R35") (pin "1") (pinfunction "1_1") (pintype "passive"))
    )
    (net (code "154") (name "TPIN_N") (class "Default")
      (node (ref "IC3") (pin "12") (pinfunction "TPIN-_12") (pintype "input"))
      (node (ref "R25") (pin "2") (pinfunction "2_2") (pintype "passive"))
      (node (ref "X5") (pin "8") (pinfunction "RX-_8") (pintype "bidirectional"))
    )
    (net (code "155") (name "TPIN_P") (class "Default")
      (node (ref "IC3") (pin "13") (pinfunction "TPIN+_13") (pintype "input"))
      (node (ref "R24") (pin "2") (pinfunction "2_2") (pintype "passive"))
      (node (ref "X5") (pin "7") (pinfunction "RX+_7") (pintype "bidirectional"))
    )
    (net (code "156") (name "TPOUT_N") (class "Default")
      (node (ref "IC3") (pin "16") (pinfunction "TPOUT-_16") (pintype "output"))
      (node (ref "R27") (pin "2") (pinfunction "2_2") (pintype "passive"))
      (node (ref "X5") (pin "2") (pinfunction "TX-_2") (pintype "bidirectional"))
    )
    (net (code "157") (name "TPOUT_P") (class "Default")
      (node (ref "IC3") (pin "17") (pinfunction "TPOUT+_17") (pintype "output"))
      (node (ref "R26") (pin "2") (pinfunction "2_2") (pintype "passive"))
      (node (ref "X5") (pin "1") (pinfunction "TX+_1") (pintype "bidirectional"))
    )
    (net (code "158") (name "TXD1") (class "Default")
      (node (ref "IC1") (pin "10") (pinfunction "T2OUT_10") (pintype "output"))
      (node (ref "X2") (pin "3") (pinfunction "3_3") (pintype "passive"))
    )
    (net (code "159") (name "UART0_CBUS0") (class "Default")
      (node (ref "IC2") (pin "15") (pinfunction "CBUS0_15") (pintype "bidirectional"))
      (node (ref "IC9") (pin "78") (pinfunction "PIN78_78") (pintype "bidirectional"))
    )
    (net (code "160") (name "UART0_CBUS1") (class "Default")
      (node (ref "IC2") (pin "14") (pinfunction "CBUS1_14") (pintype "bidirectional"))
      (node (ref "IC9") (pin "79") (pinfunction "PIN79_79") (pintype "bidirectional"))
    )
    (net (code "161") (name "UART0_LED") (class "Default")
      (node (ref "IC2") (pin "16") (pinfunction "CBUS3_16") (pintype "bidirectional"))
      (node (ref "LED1") (pin "C") (pinfunction "C_C") (pintype "passive"))
      (node (ref "X10") (pin "5") (pinfunction "5_5") (pintype "bidirectional"))
    )
    (net (code "162") (name "UART0_RXD") (class "Default")
      (node (ref "IC2") (pin "1") (pinfunction "TXD_1") (pintype "bidirectional"))
      (node (ref "IC9") (pin "81") (pinfunction "PIN81_81") (pintype "bidirectional"))
    )
    (net (code "163") (name "UART0_TXD") (class "Default")
      (node (ref "IC2") (pin "4") (pinfunction "RXD_4") (pintype "bidirectional"))
      (node (ref "IC9") (pin "80") (pinfunction "PIN80_80") (pintype "bidirectional"))
    )
    (net (code "164") (name "UART1_CTS") (class "Default")
      (node (ref "IC1") (pin "16") (pinfunction "R4OUT_16") (pintype "output"))
      (node (ref "IC9") (pin "132") (pinfunction "PIN132_132") (pintype "bidirectional"))
    )
    (net (code "165") (name "UART1_DCD") (class "Default")
      (node (ref "IC1") (pin "19") (pinfunction "R1OUT_19") (pintype "output"))
      (node (ref "IC9") (pin "127") (pinfunction "PIN127_127") (pintype "bidirectional"))
    )
    (net (code "166") (name "UART1_DSR") (class "Default")
      (node (ref "IC1") (pin "18") (pinfunction "R2OUT_18") (pintype "output"))
      (node (ref "IC9") (pin "130") (pinfunction "PIN130_130") (pintype "bidirectional"))
    )
    (net (code "167") (name "UART1_DTR") (class "Default")
      (node (ref "IC1") (pin "12") (pinfunction "T3IN_12") (pintype "input"))
      (node (ref "IC9") (pin "135") (pinfunction "PIN135_135") (pintype "bidirectional"))
    )
    (net (code "168") (name "UART1_RI") (class "Default")
      (node (ref "IC1") (pin "15") (pinfunction "R5OUT_15") (pintype "output"))
      (node (ref "IC9") (pin "134") (pinfunction "PIN134_134") (pintype "bidirectional"))
    )
    (net (code "169") (name "UART1_RTS") (class "Default")
      (node (ref "IC1") (pin "14") (pinfunction "T1IN_14") (pintype "input"))
      (node (ref "IC9") (pin "141") (pinfunction "PIN141_141") (pintype "bidirectional"))
    )
    (net (code "170") (name "UART1_RXD") (class "Default")
      (node (ref "IC1") (pin "17") (pinfunction "R3OUT_17") (pintype "output"))
      (node (ref "IC9") (pin "131") (pinfunction "PIN131_131") (pintype "bidirectional"))
    )
    (net (code "171") (name "UART1_TXD") (class "Default")
      (node (ref "IC1") (pin "13") (pinfunction "T2IN_13") (pintype "input"))
      (node (ref "IC9") (pin "140") (pinfunction "PIN140_140") (pintype "bidirectional"))
    )
    (net (code "172") (name "USBDM") (class "Default")
      (node (ref "IC2") (pin "9") (pinfunction "USBDM_9") (pintype "bidirectional"))
      (node (ref "R1") (pin "2") (pinfunction "2_2") (pintype "passive"))
    )
    (net (code "173") (name "USBDP") (class "Default")
      (node (ref "IC2") (pin "8") (pinfunction "USBDP_8") (pintype "bidirectional"))
      (node (ref "R2") (pin "2") (pinfunction "2_2") (pintype "passive"))
    )
    (net (code "174") (name "VBAT") (class "Default")
      (node (ref "IC6") (pin "3") (pinfunction "VBAT_3") (pintype "bidirectional"))
      (node (ref "R50") (pin "2") (pinfunction "2_2") (pintype "passive"))
      (node (ref "X8") (pin "P1") (pinfunction "P_P1") (pintype "bidirectional"))
    )
    (net (code "175") (name "VBUS_SENSE") (class "Default")
      (node (ref "IC2") (pin "7") (pinfunction "CBUS2_7") (pintype "bidirectional"))
      (node (ref "R3") (pin "1") (pinfunction "1_1") (pintype "passive"))
      (node (ref "R4") (pin "2") (pinfunction "2_2") (pintype "passive"))
    )
    (net (code "176") (name "VCC") (class "Default")
      (node (ref "C64") (pin "+") (pinfunction "+_+") (pintype "passive"))
      (node (ref "IC10") (pin "2") (pinfunction "VIN_2") (pintype "bidirectional"))
      (node (ref "IC13") (pin "3") (pinfunction "VIN_3") (pintype "bidirectional"))
      (node (ref "X12") (pin "1") (pinfunction "3_1") (pintype "passive"))
      (node (ref "X9") (pin "4") (pinfunction "KL_4") (pintype "passive"))
    )
    (net (code "177") (name "VGA_B0") (class "Default")
      (node (ref "IC9") (pin "106") (pinfunction "PIN106_106") (pintype "bidirectional"))
      (node (ref "R12") (pin "1") (pinfunction "1_1") (pintype "passive"))
      (node (ref "R13") (pin "1") (pinfunction "1_1") (pintype "passive"))
    )
    (net (code "178") (name "VGA_B1") (class "Default")
      (node (ref "IC9") (pin "105") (pinfunction "PIN105_105") (pintype "bidirectional"))
      (node (ref "R14") (pin "1") (pinfunction "1_1") (pintype "passive"))
    )
    (net (code "179") (name "VGA_G0") (class "Default")
      (node (ref "IC9") (pin "112") (pinfunction "PIN112_112") (pintype "bidirectional"))
      (node (ref "R9") (pin "1") (pinfunction "1_1") (pintype "passive"))
    )
    (net (code "180") (name "VGA_G1") (class "Default")
      (node (ref "IC9") (pin "111") (pinfunction "PIN111_111") (pintype "bidirectional"))
      (node (ref "R10") (pin "1") (pinfunction "1_1") (pintype "passive"))
    )
    (net (code "181") (name "VGA_G2") (class "Default")
      (node (ref "IC9") (pin "110") (pinfunction "PIN110_110") (pintype "bidirectional"))
      (node (ref "R11") (pin "1") (pinfunction "1_1") (pintype "passive"))
    )
    (net (code "182") (name "VGA_HS") (class "Default")
      (node (ref "IC9") (pin "120") (pinfunction "PIN120_120") (pintype "bidirectional"))
      (node (ref "X3") (pin "13") (pinfunction "13_13") (pintype "passive"))
    )
    (net (code "183") (name "VGA_R0") (class "Default")
      (node (ref "IC9") (pin "118") (pinfunction "PIN118_118") (pintype "bidirectional"))
      (node (ref "R6") (pin "1") (pinfunction "1_1") (pintype "passive"))
    )
    (net (code "184") (name "VGA_R1") (class "Default")
      (node (ref "IC9") (pin "114") (pinfunction "PIN114_114") (pintype "bidirectional"))
      (node (ref "R7") (pin "1") (pinfunction "1_1") (pintype "passive"))
    )
    (net (code "185") (name "VGA_R2") (class "Default")
      (node (ref "IC9") (pin "113") (pinfunction "PIN113_113") (pintype "bidirectional"))
      (node (ref "R8") (pin "1") (pinfunction "1_1") (pintype "passive"))
    )
    (net (code "186") (name "VGA_VS") (class "Default")
      (node (ref "IC9") (pin "119") (pinfunction "PIN119_119") (pintype "bidirectional"))
      (node (ref "X3") (pin "14") (pinfunction "14_14") (pintype "passive"))
    )
    (net (code "187") (name "unconnected-(IC1A-R2OUTB-Pad20)") (class "Default")
      (node (ref "IC1") (pin "20") (pinfunction "R2OUTB_20") (pintype "output"))
    )
    (net (code "188") (name "unconnected-(IC1A-~{INVALID}-Pad21)") (class "Default")
      (node (ref "IC1") (pin "21") (pinfunction "~{INVALID}_21") (pintype "output"))
    )
    (net (code "189") (name "unconnected-(IC2-CTS#-Pad6)") (class "Default")
      (node (ref "IC2") (pin "6") (pinfunction "CTS#_6") (pintype "bidirectional"))
    )
    (net (code "190") (name "unconnected-(IC2-RTS#-Pad2)") (class "Default")
      (node (ref "IC2") (pin "2") (pinfunction "RTS#_2") (pintype "bidirectional"))
    )
    (net (code "191") (name "unconnected-(IC3-CLKOUT-Pad3)") (class "Default")
      (node (ref "IC3") (pin "3") (pinfunction "CLKOUT_3") (pintype "output"))
    )
    (net (code "192") (name "unconnected-(IC3-NC*-Pad5)") (class "Default")
      (node (ref "IC3") (pin "5") (pinfunction "NC*_5") (pintype "output"))
    )
    (net (code "193") (name "unconnected-(IC7-NC1-Pad1)") (class "Default")
      (node (ref "IC7") (pin "1") (pinfunction "NC1_1") (pintype "no_connect"))
    )
    (net (code "194") (name "unconnected-(IC7-NC2-Pad2)") (class "Default")
      (node (ref "IC7") (pin "2") (pinfunction "NC2_2") (pintype "no_connect"))
    )
    (net (code "195") (name "unconnected-(IC7-NC3-Pad3)") (class "Default")
      (node (ref "IC7") (pin "3") (pinfunction "NC3_3") (pintype "no_connect"))
    )
    (net (code "196") (name "unconnected-(IC9A-ADC_VREF-Pad5)") (class "Default")
      (node (ref "IC9") (pin "5") (pinfunction "ADC_VREF_5") (pintype "bidirectional"))
    )
    (net (code "197") (name "unconnected-(IC12-AREF-Pad20)") (class "Default")
      (node (ref "IC12") (pin "20") (pinfunction "AREF_20") (pintype "input"))
    )
    (net (code "198") (name "unconnected-(IC12-PB0(PCINT0{slash}CLKO{slash}ICP1)-Pad12)") (class "Default")
      (node (ref "IC12") (pin "12") (pinfunction "PB0(PCINT0/CLKO/ICP1)_12") (pintype "bidirectional"))
    )
    (net (code "199") (name "unconnected-(IC12-PB1(PCINT1{slash}OC1A)-Pad13)") (class "Default")
      (node (ref "IC12") (pin "13") (pinfunction "PB1(PCINT1/OC1A)_13") (pintype "bidirectional"))
    )
    (net (code "200") (name "unconnected-(IC12-PC0(ADC0{slash}PCINT8)-Pad23)") (class "Default")
      (node (ref "IC12") (pin "23") (pinfunction "PC0(ADC0/PCINT8)_23") (pintype "bidirectional"))
    )
    (net (code "201") (name "unconnected-(IC12-PC1(ADC1{slash}PCINT9)-Pad24)") (class "Default")
      (node (ref "IC12") (pin "24") (pinfunction "PC1(ADC1/PCINT9)_24") (pintype "bidirectional"))
    )
    (net (code "202") (name "unconnected-(IC12-PC2(ADC2{slash}PCINT10)-Pad25)") (class "Default")
      (node (ref "IC12") (pin "25") (pinfunction "PC2(ADC2/PCINT10)_25") (pintype "bidirectional"))
    )
    (net (code "203") (name "unconnected-(IC12-PC3(ADC3{slash}PCINT11)-Pad26)") (class "Default")
      (node (ref "IC12") (pin "26") (pinfunction "PC3(ADC3/PCINT11)_26") (pintype "bidirectional"))
    )
    (net (code "204") (name "unconnected-(IC12-PD3(PCINT19{slash}OC2B{slash}INT1)-Pad1)") (class "Default")
      (node (ref "IC12") (pin "1") (pinfunction "PD3(PCINT19/OC2B/INT1)_1") (pintype "bidirectional"))
    )
    (net (code "205") (name "unconnected-(IC12-PD4(PCINT20{slash}XCK{slash}T0)-Pad2)") (class "Default")
      (node (ref "IC12") (pin "2") (pinfunction "PD4(PCINT20/XCK/T0)_2") (pintype "bidirectional"))
    )
    (net (code "206") (name "unconnected-(IC12-PE0(ACO)-Pad3)") (class "Default")
      (node (ref "IC12") (pin "3") (pinfunction "PE0(ACO)_3") (pintype "bidirectional"))
    )
    (net (code "207") (name "unconnected-(IC12-PE1-Pad6)") (class "Default")
      (node (ref "IC12") (pin "6") (pinfunction "PE1_6") (pintype "bidirectional"))
    )
    (net (code "208") (name "unconnected-(IC12-PE2(ADC6)-Pad19)") (class "Default")
      (node (ref "IC12") (pin "19") (pinfunction "PE2(ADC6)_19") (pintype "bidirectional"))
    )
    (net (code "209") (name "unconnected-(IC12-PE3(ADC7)-Pad22)") (class "Default")
      (node (ref "IC12") (pin "22") (pinfunction "PE3(ADC7)_22") (pintype "bidirectional"))
    )
    (net (code "210") (name "unconnected-(S1-Pad2)") (class "Default")
      (node (ref "S1") (pin "2") (pinfunction "2_2") (pintype "passive"))
    )
    (net (code "211") (name "unconnected-(S2-Pad2)") (class "Default")
      (node (ref "S2") (pin "2") (pinfunction "2_2") (pintype "passive"))
    )
    (net (code "212") (name "unconnected-(X1-Pad4)") (class "Default")
      (node (ref "X1") (pin "4") (pinfunction "4_4") (pintype "input"))
    )
    (net (code "213") (name "unconnected-(X3-Pad4)") (class "Default")
      (node (ref "X3") (pin "4") (pinfunction "4_4") (pintype "passive"))
    )
    (net (code "214") (name "unconnected-(X3-Pad9)") (class "Default")
      (node (ref "X3") (pin "9") (pinfunction "9_9") (pintype "passive"))
    )
    (net (code "215") (name "unconnected-(X3-Pad11)") (class "Default")
      (node (ref "X3") (pin "11") (pinfunction "11_11") (pintype "passive"))
    )
    (net (code "216") (name "unconnected-(X3-Pad12)") (class "Default")
      (node (ref "X3") (pin "12") (pinfunction "12_12") (pintype "passive"))
    )
    (net (code "217") (name "unconnected-(X3-Pad15)") (class "Default")
      (node (ref "X3") (pin "15") (pinfunction "15_15") (pintype "passive"))
    )
    (net (code "218") (name "unconnected-(X5-NC1-Pad4)") (class "Default")
      (node (ref "X5") (pin "4") (pinfunction "NC1_4") (pintype "no_connect"))
    )
    (net (code "219") (name "unconnected-(X5-NC2-Pad5)") (class "Default")
      (node (ref "X5") (pin "5") (pinfunction "NC2_5") (pintype "no_connect"))
    )
    (net (code "220") (name "unconnected-(X5-NC3-Pad6)") (class "Default")
      (node (ref "X5") (pin "6") (pinfunction "NC3_6") (pintype "no_connect"))
    )
    (net (code "221") (name "unconnected-(X6-RING_SW-Pad5)") (class "Default")
      (node (ref "X6") (pin "5") (pinfunction "RING_SW_5") (pintype "bidirectional"))
    )
    (net (code "222") (name "unconnected-(X6-TIP_SW-Pad4)") (class "Default")
      (node (ref "X6") (pin "4") (pinfunction "TIP_SW_4") (pintype "bidirectional"))
    )
    (net (code "223") (name "unconnected-(X11G-KL-Pad6)") (class "Default")
      (node (ref "X11") (pin "6") (pinfunction "KL_6") (pintype "passive"))
    )
    (net (code "224") (name "unconnected-(X11H-KL-Pad7)") (class "Default")
      (node (ref "X11") (pin "7") (pinfunction "KL_7") (pintype "passive"))
    )
    (net (code "225") (name "unconnected-(X11I-KL-Pad8)") (class "Default")
      (node (ref "X11") (pin "8") (pinfunction "KL_8") (pintype "passive"))
    )
  )
)
